# RA6M1.net
KiCad netlist of a schematic drawn in Altium Designer
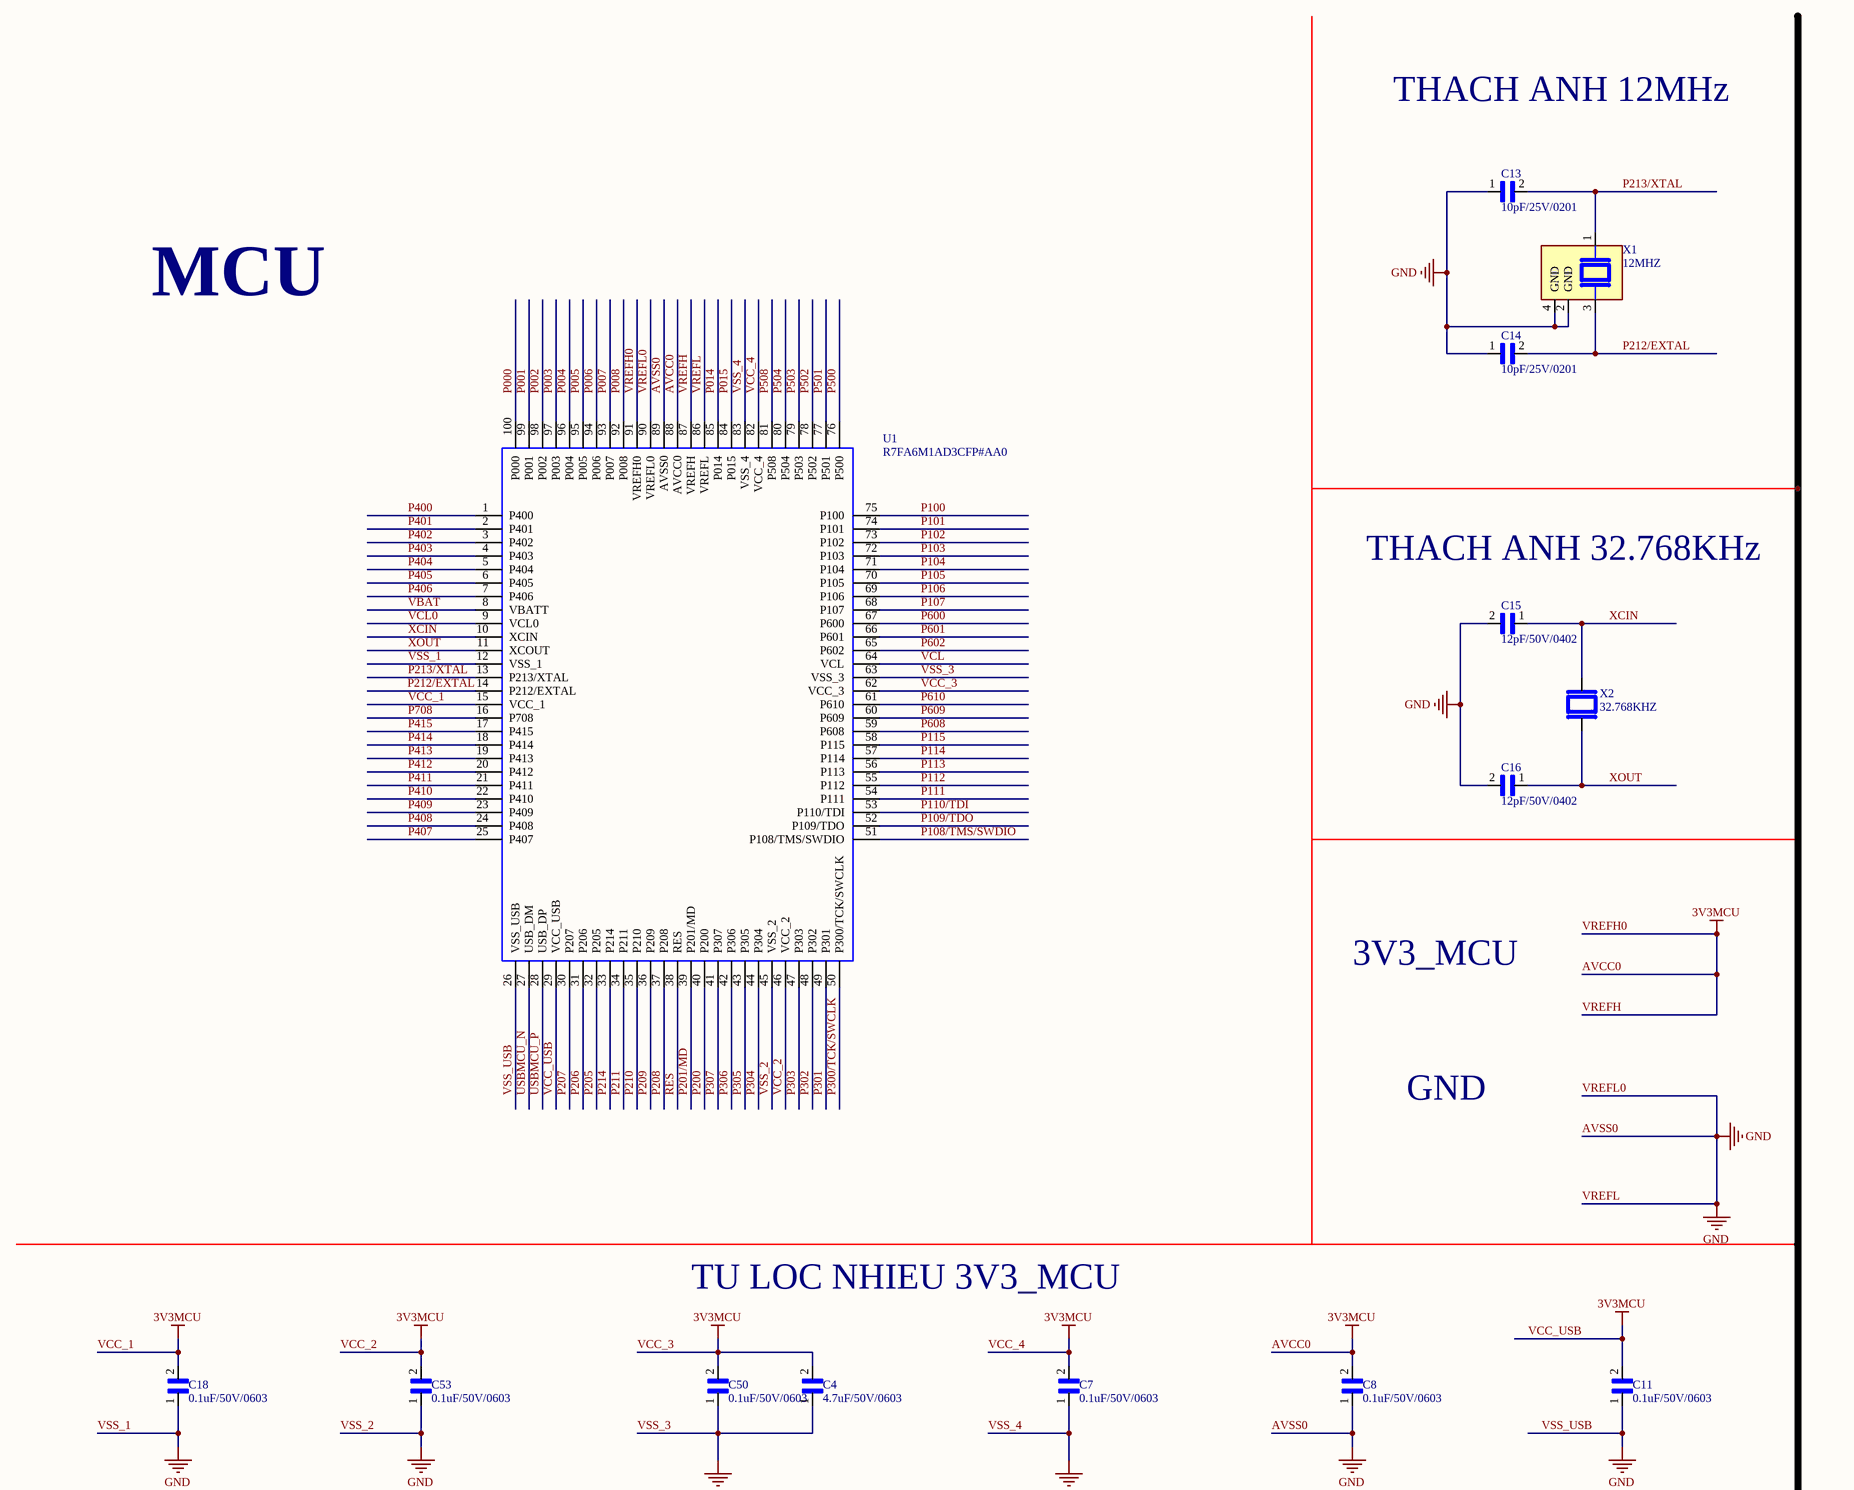
[diagram p0: RA6M1.SchDoc, top left]
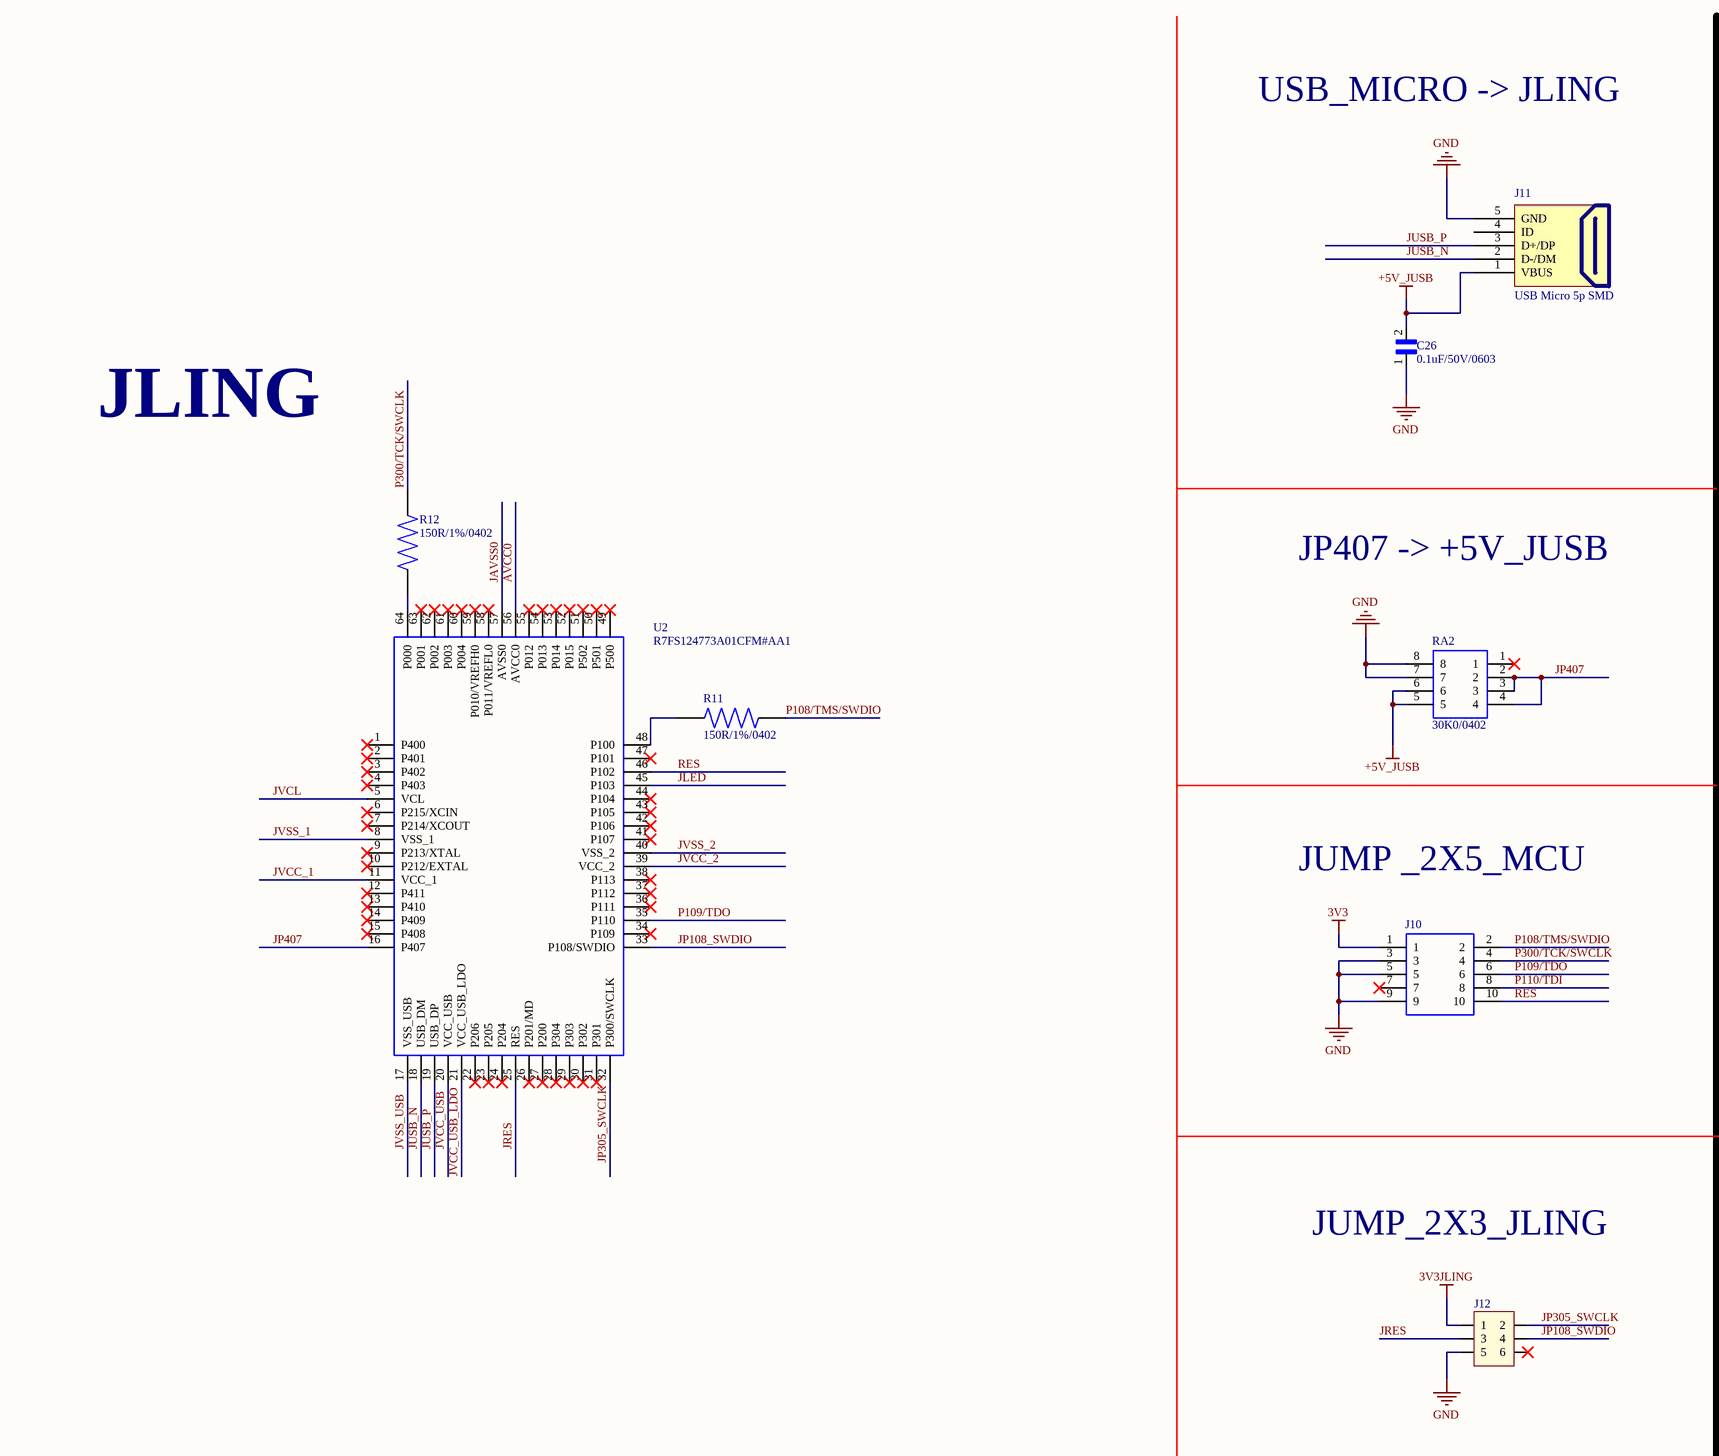
[diagram p1: RA6M1.SchDoc, top middle]
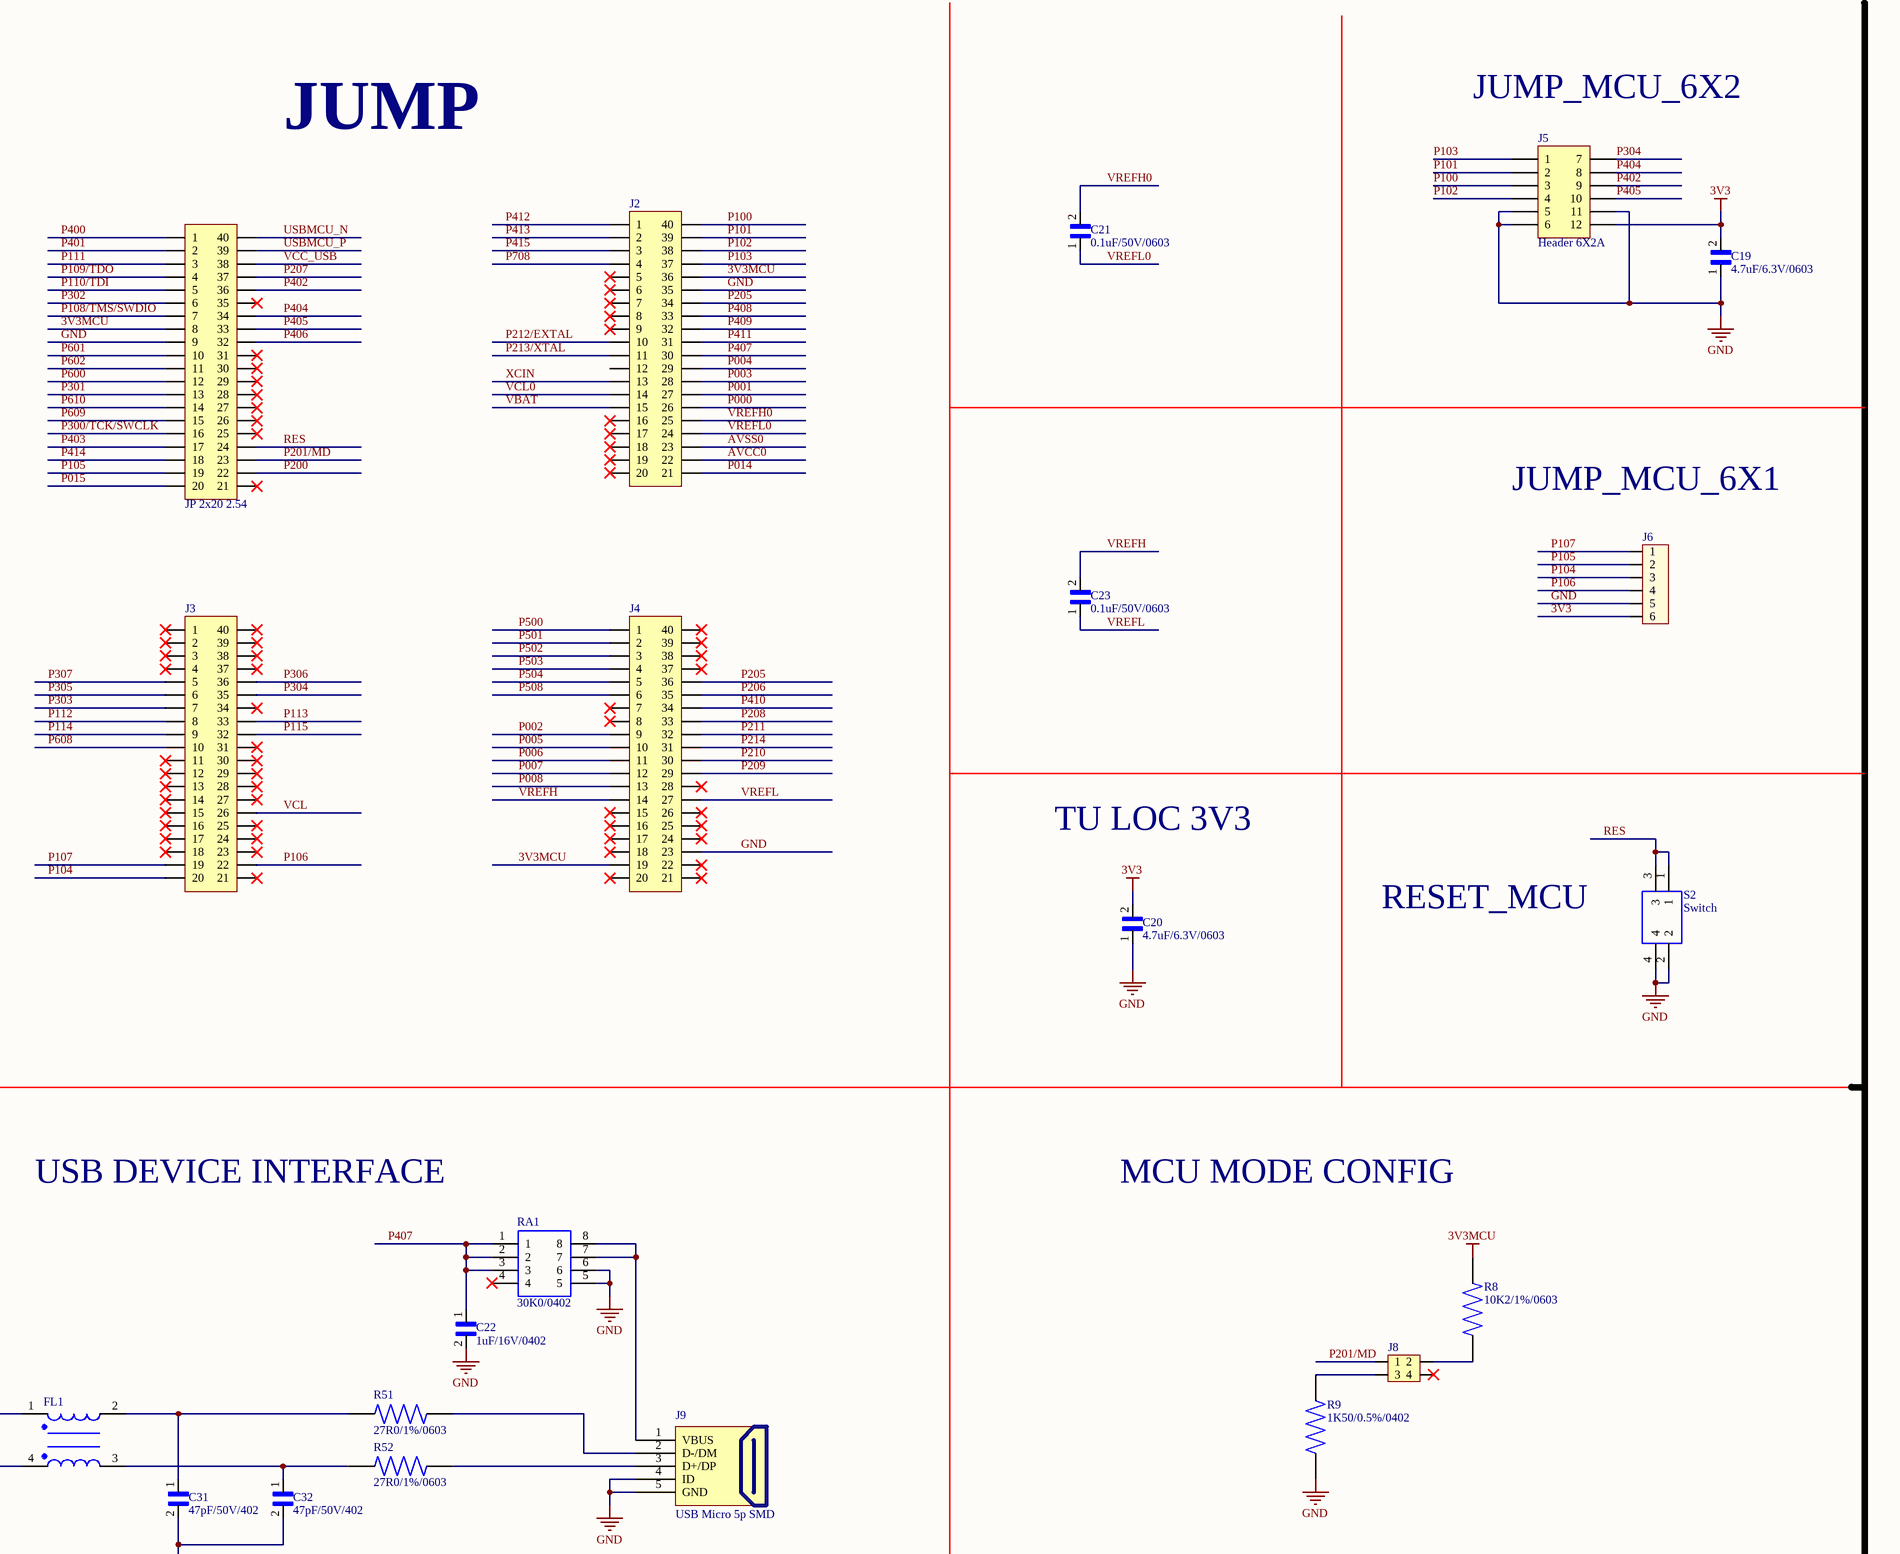
[diagram p2: RA6M1.SchDoc, top right]
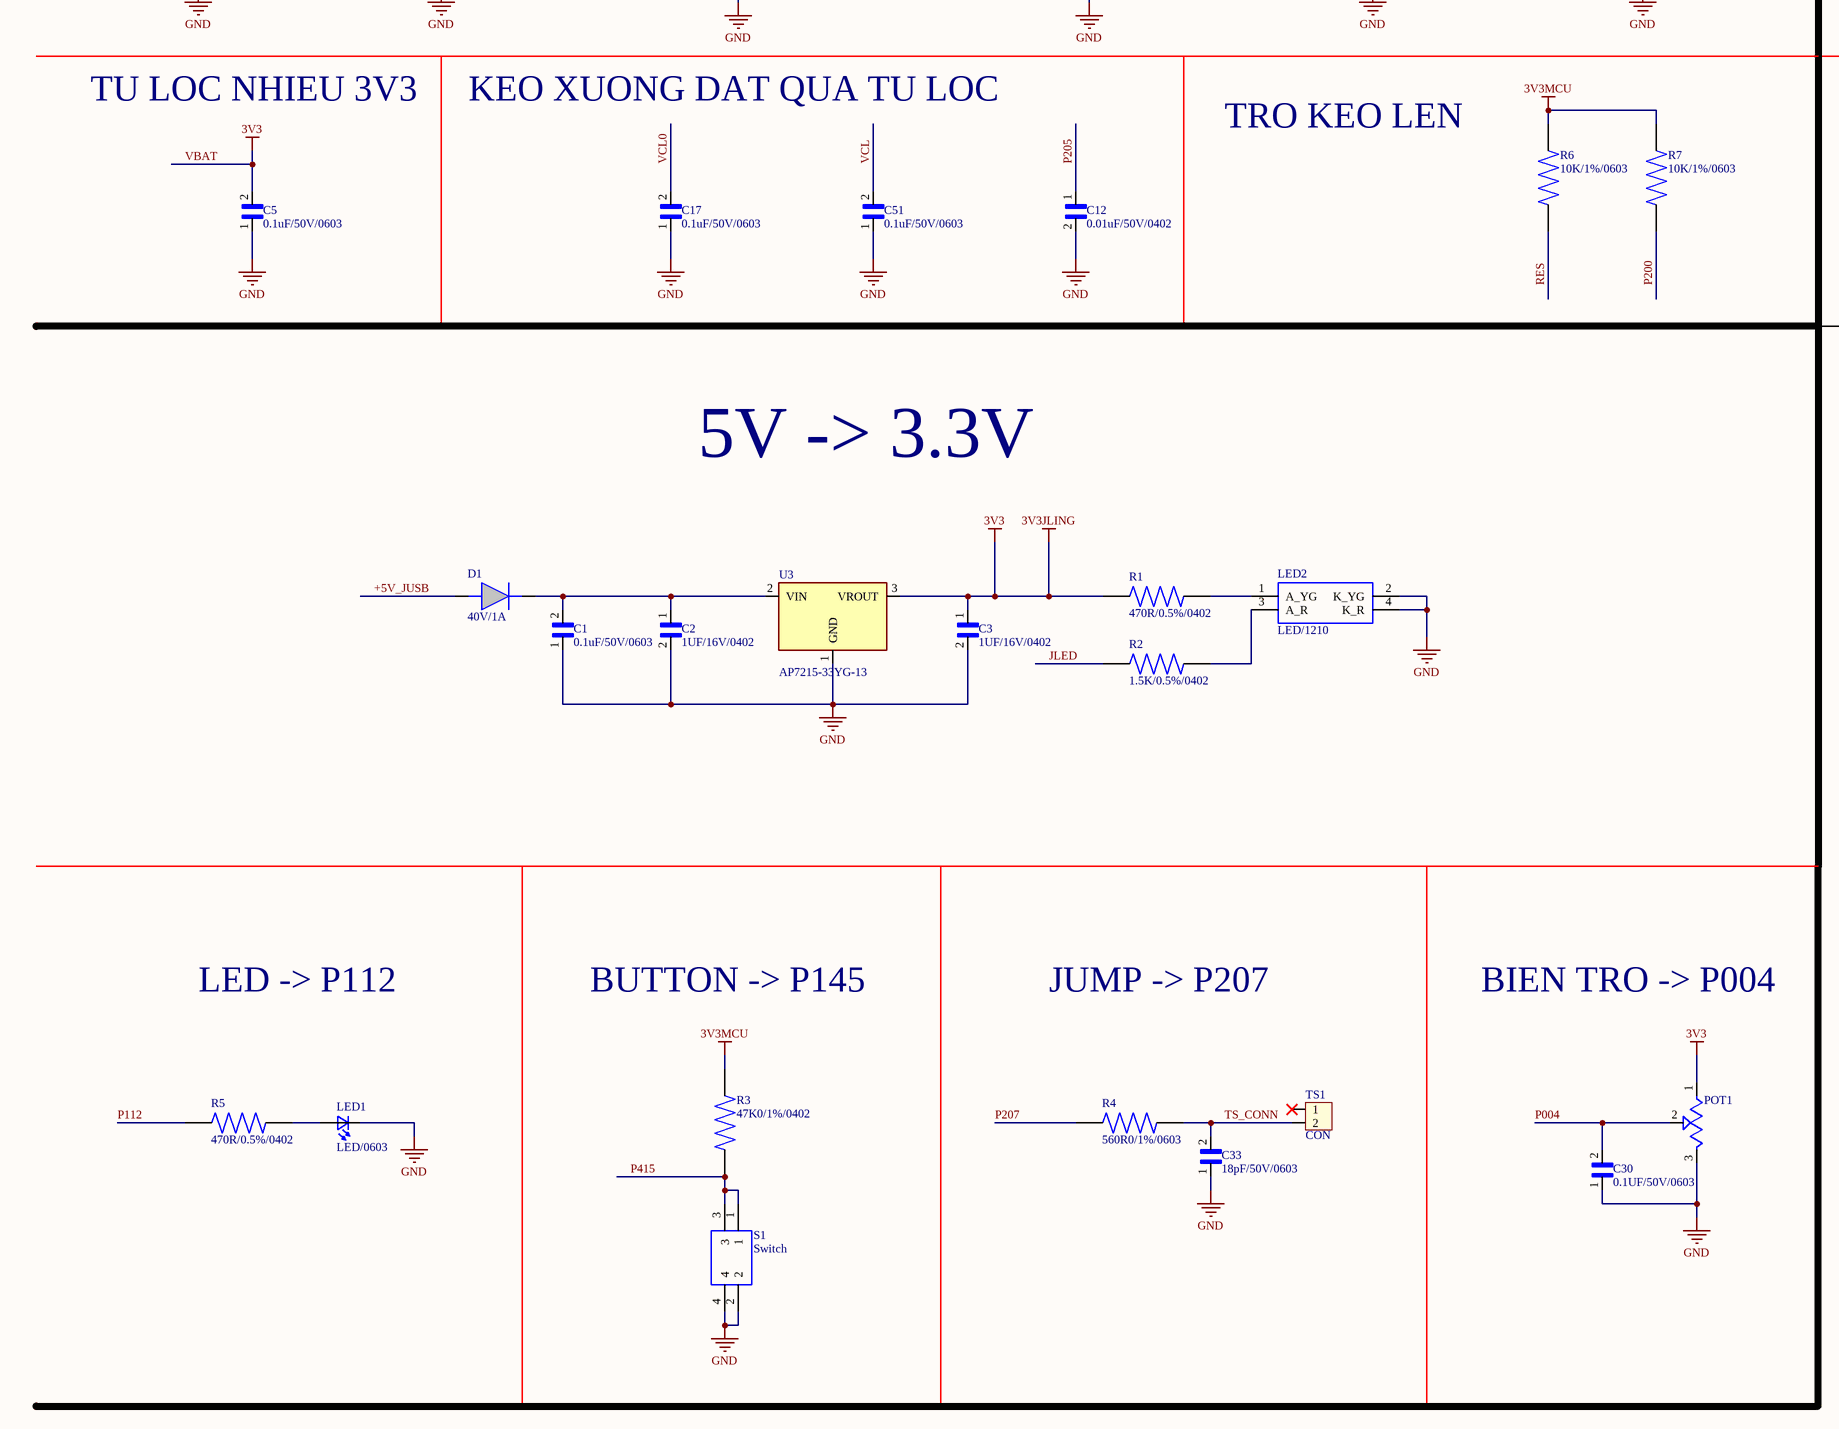
[diagram p3: RA6M1.SchDoc, bottom left]
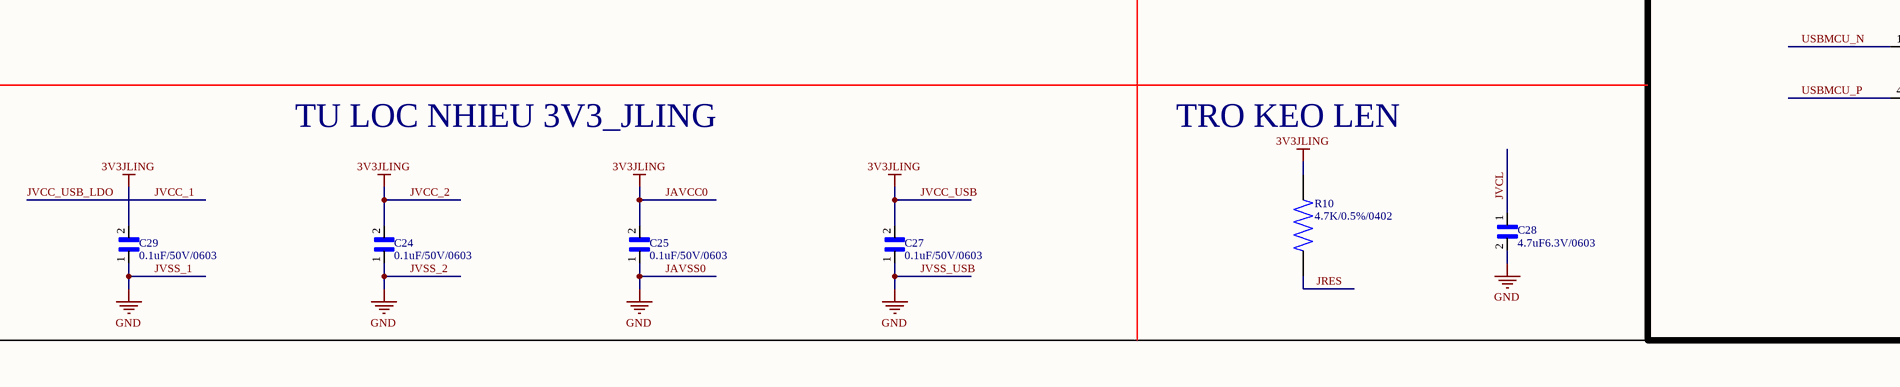
[diagram p4: RA6M1.SchDoc, bottom middle]
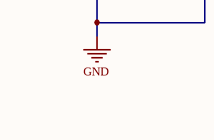
[diagram p5: RA6M1.SchDoc, bottom right]

(export (version "E")
  (design (tool "Eeschema 10.0.6"))
  (components
    (comp (ref "C1")
      (value "0.1uF/50V/0603")
      (footprint "CAPC1608X90N")
      (description "0.1ÂµF Â±10% 50V Ceramic Capacitor X7R 0603 _1608 Metric_")
      (fields (field (name "MP") "CL10B104KB8NNNC") (field (name "MF") "Samsung Electro-Mechanics"))
      (libsource (lib "RA6M1_DONE") (part "CL10B104KB8NNNC"))
    )
    (comp (ref "C2")
      (value "1UF/16V/0402")
      (footprint "CAPC1005X55N")
      (description "1ÂµF Â±10% 16V Ceramic Capacitor X5R 0402 (1005 Metric)")
      (fields (field (name "MP") "CL05A105KO5NNNC") (field (name "MF") "Samsung Electro-Mechanics"))
      (libsource (lib "RA6M1_DONE") (part "CL05A105KO5NNNC"))
    )
    (comp (ref "C3")
      (value "1UF/16V/0402")
      (footprint "CAPC1005X55N")
      (description "1ÂµF Â±10% 16V Ceramic Capacitor X5R 0402 (1005 Metric)")
      (fields (field (name "MP") "CL05A105KO5NNNC") (field (name "MF") "Samsung Electro-Mechanics"))
      (libsource (lib "RA6M1_DONE") (part "CL05A105KO5NNNC"))
    )
    (comp (ref "C4")
      (value "4.7uF/50V/0603")
      (footprint "CAPC1608X90N")
      (description "0.1ÂµF Â±10% 50V Ceramic Capacitor X7R 0603 _1608 Metric_")
      (fields (field (name "MP") "CL10B104KB8NNNC") (field (name "MF") "Samsung Electro-Mechanics"))
      (libsource (lib "RA6M1_DONE") (part "CL10B104KB8NNNC"))
    )
    (comp (ref "C5")
      (value "0.1uF/50V/0603")
      (footprint "CAPC1608X90N")
      (description "0.1ÂµF Â±10% 50V Ceramic Capacitor X7R 0603 _1608 Metric_")
      (fields (field (name "MP") "CL10B104KB8NNNC") (field (name "MF") "Samsung Electro-Mechanics"))
      (libsource (lib "RA6M1_DONE") (part "CL10B104KB8NNNC"))
    )
    (comp (ref "C7")
      (value "0.1uF/50V/0603")
      (footprint "CAPC1608X90N")
      (description "0.1ÂµF Â±10% 50V Ceramic Capacitor X7R 0603 _1608 Metric_")
      (fields (field (name "MP") "CL10B104KB8NNNC") (field (name "MF") "Samsung Electro-Mechanics"))
      (libsource (lib "RA6M1_DONE") (part "CL10B104KB8NNNC"))
    )
    (comp (ref "C8")
      (value "0.1uF/50V/0603")
      (footprint "CAPC1608X90N")
      (description "0.1ÂµF Â±10% 50V Ceramic Capacitor X7R 0603 _1608 Metric_")
      (fields (field (name "MP") "CL10B104KB8NNNC") (field (name "MF") "Samsung Electro-Mechanics"))
      (libsource (lib "RA6M1_DONE") (part "CL10B104KB8NNNC"))
    )
    (comp (ref "C11")
      (value "0.1uF/50V/0603")
      (footprint "CAPC1608X90N")
      (description "0.1ÂµF Â±10% 50V Ceramic Capacitor X7R 0603 _1608 Metric_")
      (fields (field (name "MP") "CL10B104KB8NNNC") (field (name "MF") "Samsung Electro-Mechanics"))
      (libsource (lib "RA6M1_DONE") (part "CL10B104KB8NNNC"))
    )
    (comp (ref "C12")
      (value "0.01uF/50V/0402")
      (footprint "CAPC1005X55N")
      (description "1ÂµF Â±10% 16V Ceramic Capacitor X5R 0402 (1005 Metric)")
      (fields (field (name "MP") "CL05A105KO5NNNC") (field (name "MF") "Samsung Electro-Mechanics"))
      (libsource (lib "RA6M1_DONE") (part "CL05A105KO5NNNC"))
    )
    (comp (ref "C13")
      (value "10pF/25V/0201")
      (footprint "RESC0603X26N")
      (description "TU0201")
      (fields (field (name "MP") "CL10B104KB8NNNC") (field (name "MF") "Samsung Electro-Mechanics"))
      (libsource (lib "Tu0201") (part "RESC0603X26N"))
    )
    (comp (ref "C14")
      (value "10pF/25V/0201")
      (footprint "RESC0603X26N")
      (description "TU0201")
      (fields (field (name "MP") "CL10B104KB8NNNC") (field (name "MF") "Samsung Electro-Mechanics"))
      (libsource (lib "Tu0201") (part "RESC0603X26N"))
    )
    (comp (ref "C15")
      (value "12pF/50V/0402")
      (footprint "CAPC1005X55N")
      (description "1ÂµF Â±10% 16V Ceramic Capacitor X5R 0402 (1005 Metric)")
      (fields (field (name "MP") "CL05A105KO5NNNC") (field (name "MF") "Samsung Electro-Mechanics"))
      (libsource (lib "") (part "CL05A105KO5NNNC_1"))
    )
    (comp (ref "C16")
      (value "12pF/50V/0402")
      (footprint "CAPC1005X55N")
      (description "1ÂµF Â±10% 16V Ceramic Capacitor X5R 0402 (1005 Metric)")
      (fields (field (name "MP") "CL05A105KO5NNNC") (field (name "MF") "Samsung Electro-Mechanics"))
      (libsource (lib "") (part "CL05A105KO5NNNC_1"))
    )
    (comp (ref "C17")
      (value "0.1uF/50V/0603")
      (footprint "CAPC1608X90N")
      (description "0.1ÂµF Â±10% 50V Ceramic Capacitor X7R 0603 _1608 Metric_")
      (fields (field (name "MP") "CL10B104KB8NNNC") (field (name "MF") "Samsung Electro-Mechanics"))
      (libsource (lib "RA6M1_DONE") (part "CL10B104KB8NNNC"))
    )
    (comp (ref "C18")
      (value "0.1uF/50V/0603")
      (footprint "CAPC1608X90N")
      (description "0.1ÂµF Â±10% 50V Ceramic Capacitor X7R 0603 _1608 Metric_")
      (fields (field (name "MP") "CL10B104KB8NNNC") (field (name "MF") "Samsung Electro-Mechanics"))
      (libsource (lib "RA6M1_DONE") (part "CL10B104KB8NNNC"))
    )
    (comp (ref "C19")
      (value "4.7uF/6.3V/0603")
      (footprint "CAPC1608X90N")
      (description "0.1ÂµF Â±10% 50V Ceramic Capacitor X7R 0603 _1608 Metric_")
      (fields (field (name "MP") "CL10B104KB8NNNC") (field (name "MF") "Samsung Electro-Mechanics"))
      (libsource (lib "RA6M1_DONE") (part "CL10B104KB8NNNC"))
    )
    (comp (ref "C20")
      (value "4.7uF/6.3V/0603")
      (footprint "CAPC1608X90N")
      (description "0.1ÂµF Â±10% 50V Ceramic Capacitor X7R 0603 _1608 Metric_")
      (fields (field (name "MP") "CL10B104KB8NNNC") (field (name "MF") "Samsung Electro-Mechanics"))
      (libsource (lib "RA6M1_DONE") (part "CL10B104KB8NNNC"))
    )
    (comp (ref "C21")
      (value "0.1uF/50V/0603")
      (footprint "CAPC1608X90N")
      (description "0.1ÂµF Â±10% 50V Ceramic Capacitor X7R 0603 _1608 Metric_")
      (fields (field (name "MP") "CL10B104KB8NNNC") (field (name "MF") "Samsung Electro-Mechanics"))
      (libsource (lib "RA6M1_DONE") (part "CL10B104KB8NNNC"))
    )
    (comp (ref "C22")
      (value "1uF/16V/0402")
      (footprint "CAPC1005X55N")
      (description "1ÂµF Â±10% 16V Ceramic Capacitor X5R 0402 (1005 Metric)")
      (fields (field (name "MP") "CL05A105KO5NNNC") (field (name "MF") "Samsung Electro-Mechanics"))
      (libsource (lib "RA6M1_DONE") (part "CL05A105KO5NNNC"))
    )
    (comp (ref "C23")
      (value "0.1uF/50V/0603")
      (footprint "CAPC1608X90N")
      (description "0.1ÂµF Â±10% 50V Ceramic Capacitor X7R 0603 _1608 Metric_")
      (fields (field (name "MP") "CL10B104KB8NNNC") (field (name "MF") "Samsung Electro-Mechanics"))
      (libsource (lib "RA6M1_DONE") (part "CL10B104KB8NNNC"))
    )
    (comp (ref "C24")
      (value "0.1uF/50V/0603")
      (footprint "CAPC1608X90N")
      (description "0.1ÂµF Â±10% 50V Ceramic Capacitor X7R 0603 _1608 Metric_")
      (fields (field (name "MP") "CL10B104KB8NNNC") (field (name "MF") "Samsung Electro-Mechanics"))
      (libsource (lib "RA6M1_DONE") (part "CL10B104KB8NNNC"))
    )
    (comp (ref "C25")
      (value "0.1uF/50V/0603")
      (footprint "CAPC1608X90N")
      (description "0.1ÂµF Â±10% 50V Ceramic Capacitor X7R 0603 _1608 Metric_")
      (fields (field (name "MP") "CL10B104KB8NNNC") (field (name "MF") "Samsung Electro-Mechanics"))
      (libsource (lib "RA6M1_DONE") (part "CL10B104KB8NNNC"))
    )
    (comp (ref "C26")
      (value "0.1uF/50V/0603")
      (footprint "CAPC1608X90N")
      (description "0.1ÂµF Â±10% 50V Ceramic Capacitor X7R 0603 _1608 Metric_")
      (fields (field (name "MP") "CL10B104KB8NNNC") (field (name "MF") "Samsung Electro-Mechanics"))
      (libsource (lib "RA6M1_DONE") (part "CL10B104KB8NNNC"))
    )
    (comp (ref "C27")
      (value "0.1uF/50V/0603")
      (footprint "CAPC1608X90N")
      (description "0.1ÂµF Â±10% 50V Ceramic Capacitor X7R 0603 _1608 Metric_")
      (fields (field (name "MP") "CL10B104KB8NNNC") (field (name "MF") "Samsung Electro-Mechanics"))
      (libsource (lib "RA6M1_DONE") (part "CL10B104KB8NNNC"))
    )
    (comp (ref "C28")
      (value "4.7uF6.3V/0603")
      (footprint "CAPC1608X90N")
      (description "0.1ÂµF Â±10% 50V Ceramic Capacitor X7R 0603 _1608 Metric_")
      (fields (field (name "MP") "CL10B104KB8NNNC") (field (name "MF") "Samsung Electro-Mechanics"))
      (libsource (lib "") (part "CL10B104KB8NNNC_1"))
    )
    (comp (ref "C29")
      (value "0.1uF/50V/0603")
      (footprint "CAPC1608X90N")
      (description "0.1ÂµF Â±10% 50V Ceramic Capacitor X7R 0603 _1608 Metric_")
      (fields (field (name "MP") "CL10B104KB8NNNC") (field (name "MF") "Samsung Electro-Mechanics"))
      (libsource (lib "RA6M1_DONE") (part "CL10B104KB8NNNC"))
    )
    (comp (ref "C30")
      (value "0.1UF/50V/0603")
      (footprint "CAPC1608X90N")
      (description "0.1ÂµF Â±10% 50V Ceramic Capacitor X7R 0603 _1608 Metric_")
      (fields (field (name "MP") "CL10B104KB8NNNC") (field (name "MF") "Samsung Electro-Mechanics"))
      (libsource (lib "RA6M1_DONE") (part "CL10B104KB8NNNC"))
    )
    (comp (ref "C31")
      (value "47pF/50V/402")
      (footprint "CAPC1005X55N")
      (description "1ÂµF Â±10% 16V Ceramic Capacitor X5R 0402 (1005 Metric)")
      (fields (field (name "MP") "CL05A105KO5NNNC") (field (name "MF") "Samsung Electro-Mechanics"))
      (libsource (lib "RA6M1_DONE") (part "CL05A105KO5NNNC"))
    )
    (comp (ref "C32")
      (value "47pF/50V/402")
      (footprint "CAPC1005X55N")
      (description "1ÂµF Â±10% 16V Ceramic Capacitor X5R 0402 (1005 Metric)")
      (fields (field (name "MP") "CL05A105KO5NNNC") (field (name "MF") "Samsung Electro-Mechanics"))
      (libsource (lib "RA6M1_DONE") (part "CL05A105KO5NNNC"))
    )
    (comp (ref "C33")
      (value "18pF/50V/0603")
      (footprint "CAPC1608X90N")
      (description "0.1ÂµF Â±10% 50V Ceramic Capacitor X7R 0603 _1608 Metric_")
      (fields (field (name "MP") "CL10B104KB8NNNC") (field (name "MF") "Samsung Electro-Mechanics"))
      (libsource (lib "RA6M1_DONE") (part "CL10B104KB8NNNC"))
    )
    (comp (ref "C50")
      (value "0.1uF/50V/0603")
      (footprint "CAPC1608X90N")
      (description "0.1ÂµF Â±10% 50V Ceramic Capacitor X7R 0603 _1608 Metric_")
      (fields (field (name "MP") "CL10B104KB8NNNC") (field (name "MF") "Samsung Electro-Mechanics"))
      (libsource (lib "RA6M1_DONE") (part "CL10B104KB8NNNC"))
    )
    (comp (ref "C51")
      (value "0.1uF/50V/0603")
      (footprint "CAPC1608X90N")
      (description "0.1ÂµF Â±10% 50V Ceramic Capacitor X7R 0603 _1608 Metric_")
      (fields (field (name "MP") "CL10B104KB8NNNC") (field (name "MF") "Samsung Electro-Mechanics"))
      (libsource (lib "RA6M1_DONE") (part "CL10B104KB8NNNC"))
    )
    (comp (ref "C53")
      (value "0.1uF/50V/0603")
      (footprint "CAPC1608X90N")
      (description "0.1ÂµF Â±10% 50V Ceramic Capacitor X7R 0603 _1608 Metric_")
      (fields (field (name "MP") "CL10B104KB8NNNC") (field (name "MF") "Samsung Electro-Mechanics"))
      (libsource (lib "RA6M1_DONE") (part "CL10B104KB8NNNC"))
    )
    (comp (ref "D1")
      (value "40V/1A")
      (footprint "SODFL3616X98N")
      (fields
        (field (name "MANUFACTURER_PART_NUMBER") "MBR140SFT1G")
        (field (name "MOUSER PART NUMBER") "863-MBR140SFT1G")
      )
      (libsource (lib "RA6M1_DONE") (part "MBR140SFT1G"))
    )
    (comp (ref "FL1")
      (value "DLP11SN201HL2L")
      (footprint "FIL_DLP11SN201HL2L")
      (description "2 Line Common Mode Choke Surface Mount 200 Ohms @ 100MHz 110mA DCR 3.88Ohm")
      (fields (field (name "MF") "Murata"))
      (libsource (lib "RA6M1_DONE") (part "DLP11SN201HL2L"))
    )
    (comp (ref "J1")
      (value "JP 2x20 2.54")
      (footprint "JP 2x20 DT")
      (description "Cắm")
      (libsource (lib "Altium_Lib_by_KhueNguyenCreator") (part "JP 2x20 2.54 Duc Thang"))
    )
    (comp (ref "J2")
      (value "JP 2x20 2.54")
      (footprint "JP 2x20 DT")
      (description "Cắm")
      (libsource (lib "Altium_Lib_by_KhueNguyenCreator") (part "JP 2x20 2.54 Duc Thang"))
    )
    (comp (ref "J3")
      (value "JP 2x20 2.54")
      (footprint "JP 2x20 DT")
      (description "Cắm")
      (libsource (lib "Altium_Lib_by_KhueNguyenCreator") (part "JP 2x20 2.54 Duc Thang"))
    )
    (comp (ref "J4")
      (value "JP 2x20 2.54")
      (footprint "JP 2x20 DT")
      (description "Cắm")
      (libsource (lib "Altium_Lib_by_KhueNguyenCreator") (part "JP 2x20 2.54 Duc Thang"))
    )
    (comp (ref "J5")
      (value "Header 6X2A")
      (footprint "HDR2X6_CEN")
      (description "Header, 6-Pin, Dual row")
      (fields (field (name "PUBLISHER") "Altium Limited"))
      (libsource (lib "My library altium") (part "Header 6X2A"))
    )
    (comp (ref "J6")
      (value "JP6")
      (footprint "jam6")
      (description "jam 6")
      (libsource (lib "My library altium") (part "jam 6"))
    )
    (comp (ref "J8")
      (value "JP2x2")
      (footprint "HDR2X2")
      (libsource (lib "My library altium") (part "JP2x2"))
    )
    (comp (ref "J9")
      (value "USB Micro 5p SMD")
      (footprint "USB Micro 5p SMD")
      (description "USB Type B")
      (libsource (lib "Altium_Lib_by_KhueNguyenCreator") (part "USB Micro 5p SMD"))
    )
    (comp (ref "J10")
      (value "3220-10-0100-00")
      (footprint "322010010000")
      (description "Conn Shrouded Header (4 Sides) HDR 10 POS 1.27mm Solder ST Thru-Hole")
      (libsource (lib "RA6M1_DONE") (part "3220-10-0100-00"))
    )
    (comp (ref "J11")
      (value "USB Micro 5p SMD")
      (footprint "USB Micro 5p SMD")
      (description "USB Type B")
      (libsource (lib "") (part "USB Micro 5p SMD_1"))
    )
    (comp (ref "J12")
      (value "HEAD 3x2")
      (footprint "HDR2X3")
      (description "Connector 3x2")
      (libsource (lib "My library altium") (part "JP3x2"))
    )
    (comp (ref "LED1")
      (value "LED/0603")
      (footprint "0603")
      (description "http://octopart.com/ltst-c190krkt-lite-on-549893")
      (fields (field (name "MP") "LTST-C191KRKT"))
      (libsource (lib "RA6M1_DONE") (part "LTST-C191KRKT"))
    )
    (comp (ref "LED2")
      (value "LED/1210")
      (footprint "LED_597-7701-507F")
      (description "Standard LEDs - SMD Red/Green WC 80/50mcd 645/570nm")
      (fields
        (field (name "MANUFACTURER_PART_NUMBER") "598-8610-207F")
        (field (name "MOUSER PART NUMBER") "645-598-8610-207F")
      )
      (libsource (lib "RA6M1_DONE") (part "598-8610-207F"))
    )
    (comp (ref "POT1")
      (value "10K0")
      (footprint "TRIM_3352T-1-103LF")
      (description "10 kOhms 0.5W, 1/2W Through Hole Thumbwheel Potentiometer Top Adjustment")
      (fields (field (name "MP") "3352T-1-103LF") (field (name "MF") "Bourns"))
      (libsource (lib "RA6M1_DONE") (part "3352T-1-103LF"))
    )
    (comp (ref "R1")
      (value "470R/0.5%/0402")
      (footprint "RES_ERA2AED472X")
      (description "Res Thin Film 0402 4.7K Ohm 0.5% 0.063W(1/16W) 25ppm/C Molded SMD Automotive Punched T/R")
      (fields (field (name "MF") "Panasonic Electronic") (field (name "MP") "ERA-2AED472X"))
      (libsource (lib "RA6M1_DONE") (part "ERA2AED472X"))
    )
    (comp (ref "R2")
      (value "1.5K/0.5%/0402")
      (footprint "RES_ERA2AED472X")
      (description "Res Thin Film 0402 4.7K Ohm 0.5% 0.063W(1/16W) 25ppm/C Molded SMD Automotive Punched T/R")
      (fields (field (name "MF") "Panasonic Electronic") (field (name "MP") "ERA-2AED472X"))
      (libsource (lib "RA6M1_DONE") (part "ERA2AED472X"))
    )
    (comp (ref "R3")
      (value "47K0/1%/0402")
      (footprint "RES_ERA2AED472X")
      (description "Res Thin Film 0402 4.7K Ohm 0.5% 0.063W(1/16W) 25ppm/C Molded SMD Automotive Punched T/R")
      (fields (field (name "MF") "Panasonic Electronic") (field (name "MP") "ERA-2AED472X"))
      (libsource (lib "RA6M1_DONE") (part "ERA2AED472X"))
    )
    (comp (ref "R4")
      (value "560R0/1%/0603")
      (footprint "RESC1508X55N")
      (fields (field (name "MP") "RMCF0603JT27R0"))
      (libsource (lib "RA6M1_DONE") (part "RMCF0603JT27R0"))
    )
    (comp (ref "R5")
      (value "470R/0.5%/0402")
      (footprint "RES_ERA2AED472X")
      (description "Res Thin Film 0402 4.7K Ohm 0.5% 0.063W(1/16W) 25ppm/C Molded SMD Automotive Punched T/R")
      (fields (field (name "MF") "Panasonic Electronic") (field (name "MP") "ERA-2AED472X"))
      (libsource (lib "RA6M1_DONE") (part "ERA2AED472X"))
    )
    (comp (ref "R6")
      (value "10K/1%/0603")
      (footprint "RESC1508X55N")
      (fields (field (name "MP") "RMCF0603JT27R0"))
      (libsource (lib "RA6M1_DONE") (part "RMCF0603JT27R0"))
    )
    (comp (ref "R7")
      (value "10K/1%/0603")
      (footprint "RESC1508X55N")
      (fields (field (name "MP") "RMCF0603JT27R0"))
      (libsource (lib "RA6M1_DONE") (part "RMCF0603JT27R0"))
    )
    (comp (ref "R8")
      (value "10K2/1%/0603")
      (footprint "RESC1508X55N")
      (fields (field (name "MP") "RMCF0603JT27R0"))
      (libsource (lib "RA6M1_DONE") (part "RMCF0603JT27R0"))
    )
    (comp (ref "R9")
      (value "1K50/0.5%/0402")
      (footprint "RES_ERA2AED472X")
      (description "Res Thin Film 0402 4.7K Ohm 0.5% 0.063W(1/16W) 25ppm/C Molded SMD Automotive Punched T/R")
      (fields (field (name "MF") "Panasonic Electronic") (field (name "MP") "ERA-2AED472X"))
      (libsource (lib "RA6M1_DONE") (part "ERA2AED472X"))
    )
    (comp (ref "R10")
      (value "4.7K/0.5%/0402")
      (footprint "RES_ERA2AED472X")
      (description "Res Thin Film 0402 4.7K Ohm 0.5% 0.063W(1/16W) 25ppm/C Molded SMD Automotive Punched T/R")
      (fields (field (name "MF") "Panasonic Electronic") (field (name "MP") "ERA-2AED472X"))
      (libsource (lib "RA6M1_DONE") (part "ERA2AED472X"))
    )
    (comp (ref "R11")
      (value "150R/1%/0402")
      (footprint "RES_ERA2AED472X")
      (description "Res Thin Film 0402 4.7K Ohm 0.5% 0.063W(1/16W) 25ppm/C Molded SMD Automotive Punched T/R")
      (fields (field (name "MF") "Panasonic Electronic") (field (name "MP") "ERA-2AED472X"))
      (libsource (lib "RA6M1_DONE") (part "ERA2AED472X"))
    )
    (comp (ref "R12")
      (value "150R/1%/0402")
      (footprint "RES_ERA2AED472X")
      (description "Res Thin Film 0402 4.7K Ohm 0.5% 0.063W(1/16W) 25ppm/C Molded SMD Automotive Punched T/R")
      (fields (field (name "MF") "Panasonic Electronic") (field (name "MP") "ERA-2AED472X"))
      (libsource (lib "RA6M1_DONE") (part "ERA2AED472X"))
    )
    (comp (ref "R51")
      (value "27R0/1%/0603")
      (footprint "RESC1508X55N")
      (fields (field (name "MP") "RMCF0603JT27R0"))
      (libsource (lib "RA6M1_DONE") (part "RMCF0603JT27R0"))
    )
    (comp (ref "R52")
      (value "27R0/1%/0603")
      (footprint "RESC1508X55N")
      (fields (field (name "MP") "RMCF0603JT27R0"))
      (libsource (lib "RA6M1_DONE") (part "RMCF0603JT27R0"))
    )
    (comp (ref "RA1")
      (value "30K0/0402")
      (footprint "EXB28V510JX")
      (description "Resistor Networks & Arrays Resistor ArrayChip 0804 4 elements")
      (fields (field (name "MANUFACTURER_PART_NUMBER") "EXB28V303JX"))
      (libsource (lib "RA6M1_DONE") (part "EXB28V303JX"))
    )
    (comp (ref "RA2")
      (value "30K0/0402")
      (footprint "EXB28V510JX")
      (description "Resistor Networks & Arrays Resistor ArrayChip 0804 4 elements")
      (fields (field (name "MANUFACTURER_PART_NUMBER") "EXB28V303JX"))
      (libsource (lib "RA6M1_DONE") (part "EXB28V303JX"))
    )
    (comp (ref "S1")
      (value "Switch")
      (footprint "PTS645(SMT)")
      (description "C & K COMPONENTS - PTS645SM43SMTR92LFS - SWITCH, SPST, 0.05A, 12VDC, SMD, 4.3MM")
      (fields
        (field (name "MANUFACTURER_PART_NUMBER") "PTS645SM43SMTR92LFS")
        (field (name "MOUSER PART NUMBER") "611-PTS645SM43SMTR92")
      )
      (libsource (lib "RA6M1_DONE") (part "PTS645SM43SMTR92LFS"))
    )
    (comp (ref "S2")
      (value "Switch")
      (footprint "PTS645(SMT)")
      (description "C & K COMPONENTS - PTS645SM43SMTR92LFS - SWITCH, SPST, 0.05A, 12VDC, SMD, 4.3MM")
      (fields
        (field (name "MANUFACTURER_PART_NUMBER") "PTS645SM43SMTR92LFS")
        (field (name "MOUSER PART NUMBER") "611-PTS645SM43SMTR92")
      )
      (libsource (lib "RA6M1_DONE") (part "PTS645SM43SMTR92LFS"))
    )
    (comp (ref "TS1")
      (value "CON")
      (footprint "CON2")
      (description "connector 2")
      (libsource (lib "My library altium") (part "Con2"))
    )
    (comp (ref "U1")
      (value "R7FA6M1AD3CFP#AA0")
      (footprint "QFP50P1600X1600X170-100N")
      (description "ARM Cortex-M4 RA6M1 Microcontroller IC 32-Bit 120MHz 512KB (512K x 8) FLASH 100-LFQFP (14x14)")
      (fields (field (name "MOUSER PART NUMBER") "968-7FA6M1AD3CFP#AA0"))
      (libsource (lib "RA6M1_DONE") (part "R7FA6M1AD3CFP#AA0"))
    )
    (comp (ref "U2")
      (value "R7FS124773A01CFM#AA1")
      (footprint "QFP50P1200X1200X170-64N")
      (description "S124")
      (fields (field (name "MOUSER PART NUMBER") "968-124773A01CFM#AA1"))
      (libsource (lib "RA6M1_DONE") (part "R7FS124773A01CFM#AA1"))
    )
    (comp (ref "U3")
      (value "AP7215-33YG-13")
      (footprint "SOT150P400X160-3N")
      (description "Linear Voltage Regulator IC 1 Output 600mA SOT-89-3")
      (fields (field (name "MF") "Diodes Inc."))
      (libsource (lib "RA6M1_DONE") (part "AP7215-33YG-13"))
    )
    (comp (ref "X1")
      (value "12MHZ")
      (footprint "XTAL_ABM8G-12.000MHZ-B4Y-T")
      (description "12 MHz Â±30ppm Crystal 10pF 120 Ohms 4-SMD, No Lead")
      (fields (field (name "MP") "ABM8G-12.000MHZ-B4Y-T") (field (name "MF") "Abracon"))
      (libsource (lib "RA6M1_DONE") (part "ABM8G-12.000MHZ-B4Y-T"))
    )
    (comp (ref "X2")
      (value "32.768KHZ")
      (footprint "XTAL_ABS07-32.768KHZ-T")
      (description "32.768 kHz Â±20ppm Crystal 12.5pF 70 kOhms 2-SMD, No Lead")
      (fields (field (name "MP") "ABS07-32.768KHZ-T") (field (name "MF") "Abracon"))
      (libsource (lib "RA6M1_DONE") (part "ABS07-32.768KHZ-T"))
    )
  )
  (nets
    (net (code "1") (name "+5V_JUSB") (class "Default")
      (node (ref "C26") (pin "2") (pinfunction "2_2") (pintype "passive"))
      (node (ref "D1") (pin "2") (pinfunction "A_2") (pintype "passive"))
      (node (ref "J11") (pin "1") (pinfunction "VBUS_1") (pintype "passive"))
      (node (ref "RA2") (pin "5") (pinfunction "5_5") (pintype "passive"))
      (node (ref "RA2") (pin "6") (pinfunction "6_6") (pintype "passive"))
    )
    (net (code "2") (name "/JLED") (class "Default")
      (node (ref "R2") (pin "1") (pinfunction "1_1") (pintype "passive"))
      (node (ref "U2") (pin "45") (pinfunction "P103_45") (pintype "passive"))
    )
    (net (code "3") (name "/JP108_SWDIO") (class "Default")
      (node (ref "J12") (pin "4") (pinfunction "4_4") (pintype "passive"))
      (node (ref "U2") (pin "33") (pinfunction "P108/SWDIO_33") (pintype "passive"))
    )
    (net (code "4") (name "/JP305_SWCLK") (class "Default")
      (node (ref "J12") (pin "2") (pinfunction "2_2") (pintype "passive"))
      (node (ref "U2") (pin "32") (pinfunction "P300/SWCLK_32") (pintype "passive"))
    )
    (net (code "5") (name "/JP407") (class "Default")
      (node (ref "RA2") (pin "2") (pinfunction "2_2") (pintype "passive"))
      (node (ref "RA2") (pin "3") (pinfunction "3_3") (pintype "passive"))
      (node (ref "RA2") (pin "4") (pinfunction "4_4") (pintype "passive"))
      (node (ref "U2") (pin "16") (pinfunction "P407_16") (pintype "passive"))
    )
    (net (code "6") (name "/JRES") (class "Default")
      (node (ref "J12") (pin "3") (pinfunction "3_3") (pintype "passive"))
      (node (ref "R10") (pin "1") (pinfunction "1_1") (pintype "passive"))
      (node (ref "U2") (pin "25") (pinfunction "RES_25") (pintype "passive"))
    )
    (net (code "7") (name "/JUSB_N") (class "Default")
      (node (ref "J11") (pin "2") (pinfunction "D-/DM_2") (pintype "passive"))
      (node (ref "U2") (pin "18") (pinfunction "USB_DM_18") (pintype "passive"))
    )
    (net (code "8") (name "/JUSB_P") (class "Default")
      (node (ref "J11") (pin "3") (pinfunction "D+/DP_3") (pintype "passive"))
      (node (ref "U2") (pin "19") (pinfunction "USB_DP_19") (pintype "passive"))
    )
    (net (code "9") (name "/JVCC_1") (class "Default")
      (node (ref "U2") (pin "11") (pinfunction "VCC_1_11") (pintype "passive"))
      (node (ref "U2") (pin "21") (pinfunction "VCC_USB_LDO_21") (pintype "passive"))
    )
    (net (code "10") (name "/JVCL") (class "Default")
      (node (ref "C28") (pin "1") (pinfunction "1_1") (pintype "passive"))
      (node (ref "U2") (pin "5") (pinfunction "VCL_5") (pintype "passive"))
    )
    (net (code "11") (name "/P000") (class "Default")
      (node (ref "J2") (pin "26") (pinfunction "26_26") (pintype "passive"))
      (node (ref "U1") (pin "100") (pinfunction "P000_100") (pintype "passive"))
    )
    (net (code "12") (name "/P001") (class "Default")
      (node (ref "J2") (pin "27") (pinfunction "27_27") (pintype "passive"))
      (node (ref "U1") (pin "99") (pinfunction "P001_99") (pintype "passive"))
    )
    (net (code "13") (name "/P002") (class "Default")
      (node (ref "J4") (pin "9") (pinfunction "9_9") (pintype "passive"))
      (node (ref "U1") (pin "98") (pinfunction "P002_98") (pintype "passive"))
    )
    (net (code "14") (name "/P003") (class "Default")
      (node (ref "J2") (pin "28") (pinfunction "28_28") (pintype "passive"))
      (node (ref "U1") (pin "97") (pinfunction "P003_97") (pintype "passive"))
    )
    (net (code "15") (name "/P004") (class "Default")
      (node (ref "C30") (pin "2") (pinfunction "2_2") (pintype "passive"))
      (node (ref "J2") (pin "29") (pinfunction "29_29") (pintype "passive"))
      (node (ref "POT1") (pin "2") (pinfunction "WIPER_2") (pintype "passive"))
      (node (ref "U1") (pin "96") (pinfunction "P004_96") (pintype "passive"))
    )
    (net (code "16") (name "/P005") (class "Default")
      (node (ref "J4") (pin "10") (pinfunction "10_10") (pintype "passive"))
      (node (ref "U1") (pin "95") (pinfunction "P005_95") (pintype "passive"))
    )
    (net (code "17") (name "/P006") (class "Default")
      (node (ref "J4") (pin "11") (pinfunction "11_11") (pintype "passive"))
      (node (ref "U1") (pin "94") (pinfunction "P006_94") (pintype "passive"))
    )
    (net (code "18") (name "/P007") (class "Default")
      (node (ref "J4") (pin "12") (pinfunction "12_12") (pintype "passive"))
      (node (ref "U1") (pin "93") (pinfunction "P007_93") (pintype "passive"))
    )
    (net (code "19") (name "/P008") (class "Default")
      (node (ref "J4") (pin "13") (pinfunction "13_13") (pintype "passive"))
      (node (ref "U1") (pin "92") (pinfunction "P008_92") (pintype "passive"))
    )
    (net (code "20") (name "/P014") (class "Default")
      (node (ref "J2") (pin "21") (pinfunction "21_21") (pintype "passive"))
      (node (ref "U1") (pin "85") (pinfunction "P014_85") (pintype "passive"))
    )
    (net (code "21") (name "/P015") (class "Default")
      (node (ref "J1") (pin "20") (pinfunction "20_20") (pintype "passive"))
      (node (ref "U1") (pin "84") (pinfunction "P015_84") (pintype "passive"))
    )
    (net (code "22") (name "/P100") (class "Default")
      (node (ref "J2") (pin "40") (pinfunction "40_40") (pintype "passive"))
      (node (ref "J5") (pin "3") (pinfunction "3_3") (pintype "passive"))
      (node (ref "U1") (pin "75") (pinfunction "P100_75") (pintype "passive"))
    )
    (net (code "23") (name "/P101") (class "Default")
      (node (ref "J2") (pin "39") (pinfunction "39_39") (pintype "passive"))
      (node (ref "J5") (pin "2") (pinfunction "2_2") (pintype "passive"))
      (node (ref "U1") (pin "74") (pinfunction "P101_74") (pintype "passive"))
    )
    (net (code "24") (name "/P102") (class "Default")
      (node (ref "J2") (pin "38") (pinfunction "38_38") (pintype "passive"))
      (node (ref "J5") (pin "4") (pinfunction "4_4") (pintype "passive"))
      (node (ref "U1") (pin "73") (pinfunction "P102_73") (pintype "passive"))
    )
    (net (code "25") (name "/P103") (class "Default")
      (node (ref "J2") (pin "37") (pinfunction "37_37") (pintype "passive"))
      (node (ref "J5") (pin "1") (pinfunction "1_1") (pintype "passive"))
      (node (ref "U1") (pin "72") (pinfunction "P103_72") (pintype "passive"))
    )
    (net (code "26") (name "/P104") (class "Default")
      (node (ref "J3") (pin "20") (pinfunction "20_20") (pintype "passive"))
      (node (ref "J6") (pin "3") (pinfunction "3_3") (pintype "passive"))
      (node (ref "U1") (pin "71") (pinfunction "P104_71") (pintype "passive"))
    )
    (net (code "27") (name "/P105") (class "Default")
      (node (ref "J1") (pin "19") (pinfunction "19_19") (pintype "passive"))
      (node (ref "J6") (pin "2") (pinfunction "2_2") (pintype "passive"))
      (node (ref "U1") (pin "70") (pinfunction "P105_70") (pintype "passive"))
    )
    (net (code "28") (name "/P106") (class "Default")
      (node (ref "J3") (pin "22") (pinfunction "22_22") (pintype "passive"))
      (node (ref "J6") (pin "4") (pinfunction "4_4") (pintype "passive"))
      (node (ref "U1") (pin "69") (pinfunction "P106_69") (pintype "passive"))
    )
    (net (code "29") (name "/P107") (class "Default")
      (node (ref "J3") (pin "19") (pinfunction "19_19") (pintype "passive"))
      (node (ref "J6") (pin "1") (pinfunction "1_1") (pintype "passive"))
      (node (ref "U1") (pin "68") (pinfunction "P107_68") (pintype "passive"))
    )
    (net (code "30") (name "/P108{slash}TMS{slash}SWDIO") (class "Default")
      (node (ref "J1") (pin "7") (pinfunction "7_7") (pintype "passive"))
      (node (ref "J10") (pin "2") (pinfunction "2_2") (pintype "passive"))
      (node (ref "R11") (pin "2") (pinfunction "2_2") (pintype "passive"))
      (node (ref "U1") (pin "51") (pinfunction "P108/TMS/SWDIO_51") (pintype "passive"))
    )
    (net (code "31") (name "/P109{slash}TDO") (class "Default")
      (node (ref "J1") (pin "4") (pinfunction "4_4") (pintype "passive"))
      (node (ref "J10") (pin "6") (pinfunction "6_6") (pintype "passive"))
      (node (ref "U1") (pin "52") (pinfunction "P109/TDO_52") (pintype "passive"))
      (node (ref "U2") (pin "35") (pinfunction "P110_35") (pintype "passive"))
    )
    (net (code "32") (name "/P110{slash}TDI") (class "Default")
      (node (ref "J1") (pin "5") (pinfunction "5_5") (pintype "passive"))
      (node (ref "J10") (pin "8") (pinfunction "8_8") (pintype "passive"))
      (node (ref "U1") (pin "53") (pinfunction "P110/TDI_53") (pintype "passive"))
    )
    (net (code "33") (name "/P111") (class "Default")
      (node (ref "J1") (pin "3") (pinfunction "3_3") (pintype "passive"))
      (node (ref "U1") (pin "54") (pinfunction "P111_54") (pintype "passive"))
    )
    (net (code "34") (name "/P112") (class "Default")
      (node (ref "J3") (pin "8") (pinfunction "8_8") (pintype "passive"))
      (node (ref "R5") (pin "1") (pinfunction "1_1") (pintype "passive"))
      (node (ref "U1") (pin "55") (pinfunction "P112_55") (pintype "passive"))
    )
    (net (code "35") (name "/P113") (class "Default")
      (node (ref "J3") (pin "33") (pinfunction "33_33") (pintype "passive"))
      (node (ref "U1") (pin "56") (pinfunction "P113_56") (pintype "passive"))
    )
    (net (code "36") (name "/P114") (class "Default")
      (node (ref "J3") (pin "9") (pinfunction "9_9") (pintype "passive"))
      (node (ref "U1") (pin "57") (pinfunction "P114_57") (pintype "passive"))
    )
    (net (code "37") (name "/P115") (class "Default")
      (node (ref "J3") (pin "32") (pinfunction "32_32") (pintype "passive"))
      (node (ref "U1") (pin "58") (pinfunction "P115_58") (pintype "passive"))
    )
    (net (code "38") (name "/P200") (class "Default")
      (node (ref "J1") (pin "22") (pinfunction "22_22") (pintype "passive"))
      (node (ref "R7") (pin "1") (pinfunction "1_1") (pintype "passive"))
      (node (ref "U1") (pin "40") (pinfunction "P200_40") (pintype "passive"))
    )
    (net (code "39") (name "/P201{slash}MD") (class "Default")
      (node (ref "J1") (pin "23") (pinfunction "23_23") (pintype "passive"))
      (node (ref "J8") (pin "1") (pinfunction "1_1") (pintype "passive"))
      (node (ref "U1") (pin "39") (pinfunction "P201/MD_39") (pintype "passive"))
    )
    (net (code "40") (name "/P205") (class "Default")
      (node (ref "C12") (pin "1") (pinfunction "1_1") (pintype "passive"))
      (node (ref "J2") (pin "34") (pinfunction "34_34") (pintype "passive"))
      (node (ref "J4") (pin "36") (pinfunction "36_36") (pintype "passive"))
      (node (ref "U1") (pin "32") (pinfunction "P205_32") (pintype "passive"))
    )
    (net (code "41") (name "/P206") (class "Default")
      (node (ref "J4") (pin "35") (pinfunction "35_35") (pintype "passive"))
      (node (ref "U1") (pin "31") (pinfunction "P206_31") (pintype "passive"))
    )
    (net (code "42") (name "/P207") (class "Default")
      (node (ref "J1") (pin "37") (pinfunction "37_37") (pintype "passive"))
      (node (ref "R4") (pin "1") (pinfunction "1_1") (pintype "passive"))
      (node (ref "U1") (pin "30") (pinfunction "P207_30") (pintype "passive"))
    )
    (net (code "43") (name "/P208") (class "Default")
      (node (ref "J4") (pin "33") (pinfunction "33_33") (pintype "passive"))
      (node (ref "U1") (pin "37") (pinfunction "P208_37") (pintype "passive"))
    )
    (net (code "44") (name "/P209") (class "Default")
      (node (ref "J4") (pin "29") (pinfunction "29_29") (pintype "passive"))
      (node (ref "U1") (pin "36") (pinfunction "P209_36") (pintype "passive"))
    )
    (net (code "45") (name "/P210") (class "Default")
      (node (ref "J4") (pin "30") (pinfunction "30_30") (pintype "passive"))
      (node (ref "U1") (pin "35") (pinfunction "P210_35") (pintype "passive"))
    )
    (net (code "46") (name "/P211") (class "Default")
      (node (ref "J4") (pin "32") (pinfunction "32_32") (pintype "passive"))
      (node (ref "U1") (pin "34") (pinfunction "P211_34") (pintype "passive"))
    )
    (net (code "47") (name "/P212{slash}EXTAL") (class "Default")
      (node (ref "C14") (pin "2") (pinfunction "2_2") (pintype "passive"))
      (node (ref "J2") (pin "10") (pinfunction "10_10") (pintype "passive"))
      (node (ref "U1") (pin "14") (pinfunction "P212/EXTAL_14") (pintype "passive"))
      (node (ref "X1") (pin "3") (pinfunction "2_3") (pintype "passive"))
    )
    (net (code "48") (name "/P213{slash}XTAL") (class "Default")
      (node (ref "C13") (pin "2") (pinfunction "2_2") (pintype "passive"))
      (node (ref "J2") (pin "11") (pinfunction "11_11") (pintype "passive"))
      (node (ref "U1") (pin "13") (pinfunction "P213/XTAL_13") (pintype "passive"))
      (node (ref "X1") (pin "1") (pinfunction "1_1") (pintype "passive"))
    )
    (net (code "49") (name "/P214") (class "Default")
      (node (ref "J4") (pin "31") (pinfunction "31_31") (pintype "passive"))
      (node (ref "U1") (pin "33") (pinfunction "P214_33") (pintype "passive"))
    )
    (net (code "50") (name "/P300{slash}TCK{slash}SWCLK") (class "Default")
      (node (ref "J1") (pin "16") (pinfunction "16_16") (pintype "passive"))
      (node (ref "J10") (pin "4") (pinfunction "4_4") (pintype "passive"))
      (node (ref "R12") (pin "1") (pinfunction "1_1") (pintype "passive"))
      (node (ref "U1") (pin "50") (pinfunction "P300/TCK/SWCLK_50") (pintype "passive"))
    )
    (net (code "51") (name "/P301") (class "Default")
      (node (ref "J1") (pin "13") (pinfunction "13_13") (pintype "passive"))
      (node (ref "U1") (pin "49") (pinfunction "P301_49") (pintype "passive"))
    )
    (net (code "52") (name "/P302") (class "Default")
      (node (ref "J1") (pin "6") (pinfunction "6_6") (pintype "passive"))
      (node (ref "U1") (pin "48") (pinfunction "P302_48") (pintype "passive"))
    )
    (net (code "53") (name "/P303") (class "Default")
      (node (ref "J3") (pin "7") (pinfunction "7_7") (pintype "passive"))
      (node (ref "U1") (pin "47") (pinfunction "P303_47") (pintype "passive"))
    )
    (net (code "54") (name "/P304") (class "Default")
      (node (ref "J3") (pin "35") (pinfunction "35_35") (pintype "passive"))
      (node (ref "J5") (pin "7") (pinfunction "7_7") (pintype "passive"))
      (node (ref "U1") (pin "44") (pinfunction "P304_44") (pintype "passive"))
    )
    (net (code "55") (name "/P305") (class "Default")
      (node (ref "J3") (pin "6") (pinfunction "6_6") (pintype "passive"))
      (node (ref "U1") (pin "43") (pinfunction "P305_43") (pintype "passive"))
    )
    (net (code "56") (name "/P306") (class "Default")
      (node (ref "J3") (pin "36") (pinfunction "36_36") (pintype "passive"))
      (node (ref "U1") (pin "42") (pinfunction "P306_42") (pintype "passive"))
    )
    (net (code "57") (name "/P307") (class "Default")
      (node (ref "J3") (pin "5") (pinfunction "5_5") (pintype "passive"))
      (node (ref "U1") (pin "41") (pinfunction "P307_41") (pintype "passive"))
    )
    (net (code "58") (name "/P400") (class "Default")
      (node (ref "J1") (pin "1") (pinfunction "1_1") (pintype "passive"))
      (node (ref "U1") (pin "1") (pinfunction "P400_1") (pintype "passive"))
    )
    (net (code "59") (name "/P401") (class "Default")
      (node (ref "J1") (pin "2") (pinfunction "2_2") (pintype "passive"))
      (node (ref "U1") (pin "2") (pinfunction "P401_2") (pintype "passive"))
    )
    (net (code "60") (name "/P402") (class "Default")
      (node (ref "J1") (pin "36") (pinfunction "36_36") (pintype "passive"))
      (node (ref "J5") (pin "9") (pinfunction "9_9") (pintype "passive"))
      (node (ref "U1") (pin "3") (pinfunction "P402_3") (pintype "passive"))
    )
    (net (code "61") (name "/P403") (class "Default")
      (node (ref "J1") (pin "17") (pinfunction "17_17") (pintype "passive"))
      (node (ref "U1") (pin "4") (pinfunction "P403_4") (pintype "passive"))
    )
    (net (code "62") (name "/P404") (class "Default")
      (node (ref "J1") (pin "34") (pinfunction "34_34") (pintype "passive"))
      (node (ref "J5") (pin "8") (pinfunction "8_8") (pintype "passive"))
      (node (ref "U1") (pin "5") (pinfunction "P404_5") (pintype "passive"))
    )
    (net (code "63") (name "/P405") (class "Default")
      (node (ref "J1") (pin "33") (pinfunction "33_33") (pintype "passive"))
      (node (ref "J5") (pin "10") (pinfunction "10_10") (pintype "passive"))
      (node (ref "U1") (pin "6") (pinfunction "P405_6") (pintype "passive"))
    )
    (net (code "64") (name "/P406") (class "Default")
      (node (ref "J1") (pin "32") (pinfunction "32_32") (pintype "passive"))
      (node (ref "U1") (pin "7") (pinfunction "P406_7") (pintype "passive"))
    )
    (net (code "65") (name "/P407") (class "Default")
      (node (ref "C22") (pin "1") (pinfunction "1_1") (pintype "passive"))
      (node (ref "J2") (pin "30") (pinfunction "30_30") (pintype "passive"))
      (node (ref "RA1") (pin "1") (pinfunction "1_1") (pintype "passive"))
      (node (ref "RA1") (pin "2") (pinfunction "2_2") (pintype "passive"))
      (node (ref "RA1") (pin "3") (pinfunction "3_3") (pintype "passive"))
      (node (ref "U1") (pin "25") (pinfunction "P407_25") (pintype "passive"))
    )
    (net (code "66") (name "/P408") (class "Default")
      (node (ref "J2") (pin "33") (pinfunction "33_33") (pintype "passive"))
      (node (ref "U1") (pin "24") (pinfunction "P408_24") (pintype "passive"))
    )
    (net (code "67") (name "/P409") (class "Default")
      (node (ref "J2") (pin "32") (pinfunction "32_32") (pintype "passive"))
      (node (ref "U1") (pin "23") (pinfunction "P409_23") (pintype "passive"))
    )
    (net (code "68") (name "/P410") (class "Default")
      (node (ref "J4") (pin "34") (pinfunction "34_34") (pintype "passive"))
      (node (ref "U1") (pin "22") (pinfunction "P410_22") (pintype "passive"))
    )
    (net (code "69") (name "/P411") (class "Default")
      (node (ref "J2") (pin "31") (pinfunction "31_31") (pintype "passive"))
      (node (ref "U1") (pin "21") (pinfunction "P411_21") (pintype "passive"))
    )
    (net (code "70") (name "/P412") (class "Default")
      (node (ref "J2") (pin "1") (pinfunction "1_1") (pintype "passive"))
      (node (ref "U1") (pin "20") (pinfunction "P412_20") (pintype "passive"))
    )
    (net (code "71") (name "/P413") (class "Default")
      (node (ref "J2") (pin "2") (pinfunction "2_2") (pintype "passive"))
      (node (ref "U1") (pin "19") (pinfunction "P413_19") (pintype "passive"))
    )
    (net (code "72") (name "/P414") (class "Default")
      (node (ref "J1") (pin "18") (pinfunction "18_18") (pintype "passive"))
      (node (ref "U1") (pin "18") (pinfunction "P414_18") (pintype "passive"))
    )
    (net (code "73") (name "/P415") (class "Default")
      (node (ref "J2") (pin "3") (pinfunction "3_3") (pintype "passive"))
      (node (ref "R3") (pin "1") (pinfunction "1_1") (pintype "passive"))
      (node (ref "S1") (pin "1") (pinfunction "1_1") (pintype "passive"))
      (node (ref "S1") (pin "3") (pinfunction "3_3") (pintype "passive"))
      (node (ref "U1") (pin "17") (pinfunction "P415_17") (pintype "passive"))
    )
    (net (code "74") (name "/P500") (class "Default")
      (node (ref "J4") (pin "1") (pinfunction "1_1") (pintype "passive"))
      (node (ref "U1") (pin "76") (pinfunction "P500_76") (pintype "passive"))
    )
    (net (code "75") (name "/P501") (class "Default")
      (node (ref "J4") (pin "2") (pinfunction "2_2") (pintype "passive"))
      (node (ref "U1") (pin "77") (pinfunction "P501_77") (pintype "passive"))
    )
    (net (code "76") (name "/P502") (class "Default")
      (node (ref "J4") (pin "3") (pinfunction "3_3") (pintype "passive"))
      (node (ref "U1") (pin "78") (pinfunction "P502_78") (pintype "passive"))
    )
    (net (code "77") (name "/P503") (class "Default")
      (node (ref "J4") (pin "4") (pinfunction "4_4") (pintype "passive"))
      (node (ref "U1") (pin "79") (pinfunction "P503_79") (pintype "passive"))
    )
    (net (code "78") (name "/P504") (class "Default")
      (node (ref "J4") (pin "5") (pinfunction "5_5") (pintype "passive"))
      (node (ref "U1") (pin "80") (pinfunction "P504_80") (pintype "passive"))
    )
    (net (code "79") (name "/P508") (class "Default")
      (node (ref "J4") (pin "6") (pinfunction "6_6") (pintype "passive"))
      (node (ref "U1") (pin "81") (pinfunction "P508_81") (pintype "passive"))
    )
    (net (code "80") (name "/P600") (class "Default")
      (node (ref "J1") (pin "12") (pinfunction "12_12") (pintype "passive"))
      (node (ref "U1") (pin "67") (pinfunction "P600_67") (pintype "passive"))
    )
    (net (code "81") (name "/P601") (class "Default")
      (node (ref "J1") (pin "10") (pinfunction "10_10") (pintype "passive"))
      (node (ref "U1") (pin "66") (pinfunction "P601_66") (pintype "passive"))
    )
    (net (code "82") (name "/P602") (class "Default")
      (node (ref "J1") (pin "11") (pinfunction "11_11") (pintype "passive"))
      (node (ref "U1") (pin "65") (pinfunction "P602_65") (pintype "passive"))
    )
    (net (code "83") (name "/P608") (class "Default")
      (node (ref "J3") (pin "10") (pinfunction "10_10") (pintype "passive"))
      (node (ref "U1") (pin "59") (pinfunction "P608_59") (pintype "passive"))
    )
    (net (code "84") (name "/P609") (class "Default")
      (node (ref "J1") (pin "15") (pinfunction "15_15") (pintype "passive"))
      (node (ref "U1") (pin "60") (pinfunction "P609_60") (pintype "passive"))
    )
    (net (code "85") (name "/P610") (class "Default")
      (node (ref "J1") (pin "14") (pinfunction "14_14") (pintype "passive"))
      (node (ref "U1") (pin "61") (pinfunction "P610_61") (pintype "passive"))
    )
    (net (code "86") (name "/P708") (class "Default")
      (node (ref "J2") (pin "4") (pinfunction "4_4") (pintype "passive"))
      (node (ref "U1") (pin "16") (pinfunction "P708_16") (pintype "passive"))
    )
    (net (code "87") (name "/RES") (class "Default")
      (node (ref "J1") (pin "24") (pinfunction "24_24") (pintype "passive"))
      (node (ref "J10") (pin "10") (pinfunction "10_10") (pintype "passive"))
      (node (ref "R6") (pin "1") (pinfunction "1_1") (pintype "passive"))
      (node (ref "S2") (pin "1") (pinfunction "1_1") (pintype "passive"))
      (node (ref "S2") (pin "3") (pinfunction "3_3") (pintype "passive"))
      (node (ref "U1") (pin "38") (pinfunction "RES_38") (pintype "passive"))
      (node (ref "U2") (pin "46") (pinfunction "P102_46") (pintype "passive"))
    )
    (net (code "88") (name "/TS_CONN") (class "Default")
      (node (ref "C33") (pin "2") (pinfunction "2_2") (pintype "passive"))
      (node (ref "R4") (pin "2") (pinfunction "2_2") (pintype "passive"))
      (node (ref "TS1") (pin "2") (pinfunction "2_2") (pintype "passive"))
    )
    (net (code "89") (name "/USBMCU_N") (class "Default")
      (node (ref "FL1") (pin "1") (pinfunction "1_1") (pintype "passive"))
      (node (ref "J1") (pin "40") (pinfunction "40_40") (pintype "passive"))
      (node (ref "U1") (pin "27") (pinfunction "USB_DM_27") (pintype "passive"))
    )
    (net (code "90") (name "/USBMCU_P") (class "Default")
      (node (ref "FL1") (pin "4") (pinfunction "4_4") (pintype "passive"))
      (node (ref "J1") (pin "39") (pinfunction "39_39") (pintype "passive"))
      (node (ref "U1") (pin "28") (pinfunction "USB_DP_28") (pintype "passive"))
    )
    (net (code "91") (name "/VCL") (class "Default")
      (node (ref "C51") (pin "2") (pinfunction "2_2") (pintype "passive"))
      (node (ref "J3") (pin "26") (pinfunction "26_26") (pintype "passive"))
      (node (ref "U1") (pin "64") (pinfunction "VCL_64") (pintype "passive"))
    )
    (net (code "92") (name "/VCL0") (class "Default")
      (node (ref "C17") (pin "2") (pinfunction "2_2") (pintype "passive"))
      (node (ref "J2") (pin "14") (pinfunction "14_14") (pintype "passive"))
      (node (ref "U1") (pin "9") (pinfunction "VCL0_9") (pintype "passive"))
    )
    (net (code "93") (name "/XCIN") (class "Default")
      (node (ref "C15") (pin "1") (pinfunction "1_1") (pintype "passive"))
      (node (ref "J2") (pin "13") (pinfunction "13_13") (pintype "passive"))
      (node (ref "U1") (pin "10") (pinfunction "XCIN_10") (pintype "passive"))
      (node (ref "X2") (pin "1") (pinfunction "1_1") (pintype "passive"))
    )
    (net (code "94") (name "/XOUT") (class "Default")
      (node (ref "C16") (pin "1") (pinfunction "1_1") (pintype "passive"))
      (node (ref "U1") (pin "11") (pinfunction "XCOUT_11") (pintype "passive"))
      (node (ref "X2") (pin "2") (pinfunction "2_2") (pintype "passive"))
    )
    (net (code "95") (name "3V3") (class "Default")
      (node (ref "C19") (pin "2") (pinfunction "2_2") (pintype "passive"))
      (node (ref "C20") (pin "2") (pinfunction "2_2") (pintype "passive"))
      (node (ref "C24") (pin "2") (pinfunction "2_2") (pintype "passive"))
      (node (ref "C25") (pin "2") (pinfunction "2_2") (pintype "passive"))
      (node (ref "C27") (pin "2") (pinfunction "2_2") (pintype "passive"))
      (node (ref "C29") (pin "2") (pinfunction "2_2") (pintype "passive"))
      (node (ref "C3") (pin "1") (pinfunction "1_1") (pintype "passive"))
      (node (ref "C5") (pin "2") (pinfunction "2_2") (pintype "passive"))
      (node (ref "J10") (pin "1") (pinfunction "1_1") (pintype "passive"))
      (node (ref "J12") (pin "1") (pinfunction "1_1") (pintype "passive"))
      (node (ref "J2") (pin "15") (pinfunction "15_15") (pintype "passive"))
      (node (ref "J5") (pin "12") (pinfunction "12_12") (pintype "passive"))
      (node (ref "J6") (pin "6") (pinfunction "6_6") (pintype "passive"))
      (node (ref "POT1") (pin "1") (pinfunction "CCW_1") (pintype "passive"))
      (node (ref "R1") (pin "1") (pinfunction "1_1") (pintype "passive"))
      (node (ref "R10") (pin "2") (pinfunction "2_2") (pintype "passive"))
      (node (ref "U1") (pin "8") (pinfunction "VBATT_8") (pintype "passive"))
      (node (ref "U2") (pin "20") (pinfunction "VCC_USB_20") (pintype "passive"))
      (node (ref "U2") (pin "39") (pinfunction "VCC_2_39") (pintype "passive"))
      (node (ref "U3") (pin "3") (pinfunction "VROUT_3") (pintype "power_in"))
    )
    (net (code "96") (name "3V3MCU") (class "Default")
      (node (ref "C11") (pin "2") (pinfunction "2_2") (pintype "passive"))
      (node (ref "C18") (pin "2") (pinfunction "2_2") (pintype "passive"))
      (node (ref "C21") (pin "2") (pinfunction "2_2") (pintype "passive"))
      (node (ref "C23") (pin "2") (pinfunction "2_2") (pintype "passive"))
      (node (ref "C4") (pin "2") (pinfunction "2_2") (pintype "passive"))
      (node (ref "C50") (pin "2") (pinfunction "2_2") (pintype "passive"))
      (node (ref "C53") (pin "2") (pinfunction "2_2") (pintype "passive"))
      (node (ref "C7") (pin "2") (pinfunction "2_2") (pintype "passive"))
      (node (ref "C8") (pin "2") (pinfunction "2_2") (pintype "passive"))
      (node (ref "J1") (pin "38") (pinfunction "38_38") (pintype "passive"))
      (node (ref "J1") (pin "8") (pinfunction "8_8") (pintype "passive"))
      (node (ref "J2") (pin "22") (pinfunction "22_22") (pintype "passive"))
      (node (ref "J2") (pin "25") (pinfunction "25_25") (pintype "passive"))
      (node (ref "J2") (pin "36") (pinfunction "36_36") (pintype "passive"))
      (node (ref "J4") (pin "14") (pinfunction "14_14") (pintype "passive"))
      (node (ref "J4") (pin "19") (pinfunction "19_19") (pintype "passive"))
      (node (ref "R3") (pin "2") (pinfunction "2_2") (pintype "passive"))
      (node (ref "R6") (pin "2") (pinfunction "2_2") (pintype "passive"))
      (node (ref "R7") (pin "2") (pinfunction "2_2") (pintype "passive"))
      (node (ref "R8") (pin "2") (pinfunction "2_2") (pintype "passive"))
      (node (ref "U1") (pin "15") (pinfunction "VCC_1_15") (pintype "passive"))
      (node (ref "U1") (pin "29") (pinfunction "VCC_USB_29") (pintype "passive"))
      (node (ref "U1") (pin "46") (pinfunction "VCC_2_46") (pintype "passive"))
      (node (ref "U1") (pin "62") (pinfunction "VCC_3_62") (pintype "passive"))
      (node (ref "U1") (pin "82") (pinfunction "VCC_4_82") (pintype "passive"))
      (node (ref "U1") (pin "87") (pinfunction "VREFH_87") (pintype "passive"))
      (node (ref "U1") (pin "88") (pinfunction "AVCC0_88") (pintype "passive"))
      (node (ref "U1") (pin "91") (pinfunction "VREFH0_91") (pintype "passive"))
      (node (ref "U2") (pin "56") (pinfunction "AVCC0_56") (pintype "passive"))
    )
    (net (code "97") (name "GND") (class "Default")
      (node (ref "C1") (pin "1") (pinfunction "1_1") (pintype "passive"))
      (node (ref "C11") (pin "1") (pinfunction "1_1") (pintype "passive"))
      (node (ref "C12") (pin "2") (pinfunction "2_2") (pintype "passive"))
      (node (ref "C13") (pin "1") (pinfunction "1_1") (pintype "passive"))
      (node (ref "C14") (pin "1") (pinfunction "1_1") (pintype "passive"))
      (node (ref "C15") (pin "2") (pinfunction "2_2") (pintype "passive"))
      (node (ref "C16") (pin "2") (pinfunction "2_2") (pintype "passive"))
      (node (ref "C17") (pin "1") (pinfunction "1_1") (pintype "passive"))
      (node (ref "C18") (pin "1") (pinfunction "1_1") (pintype "passive"))
      (node (ref "C19") (pin "1") (pinfunction "1_1") (pintype "passive"))
      (node (ref "C2") (pin "2") (pinfunction "2_2") (pintype "passive"))
      (node (ref "C20") (pin "1") (pinfunction "1_1") (pintype "passive"))
      (node (ref "C21") (pin "1") (pinfunction "1_1") (pintype "passive"))
      (node (ref "C22") (pin "2") (pinfunction "2_2") (pintype "passive"))
      (node (ref "C23") (pin "1") (pinfunction "1_1") (pintype "passive"))
      (node (ref "C24") (pin "1") (pinfunction "1_1") (pintype "passive"))
      (node (ref "C25") (pin "1") (pinfunction "1_1") (pintype "passive"))
      (node (ref "C26") (pin "1") (pinfunction "1_1") (pintype "passive"))
      (node (ref "C27") (pin "1") (pinfunction "1_1") (pintype "passive"))
      (node (ref "C28") (pin "2") (pinfunction "2_2") (pintype "passive"))
      (node (ref "C29") (pin "1") (pinfunction "1_1") (pintype "passive"))
      (node (ref "C3") (pin "2") (pinfunction "2_2") (pintype "passive"))
      (node (ref "C30") (pin "1") (pinfunction "1_1") (pintype "passive"))
      (node (ref "C31") (pin "2") (pinfunction "2_2") (pintype "passive"))
      (node (ref "C32") (pin "2") (pinfunction "2_2") (pintype "passive"))
      (node (ref "C33") (pin "1") (pinfunction "1_1") (pintype "passive"))
      (node (ref "C4") (pin "1") (pinfunction "1_1") (pintype "passive"))
      (node (ref "C5") (pin "1") (pinfunction "1_1") (pintype "passive"))
      (node (ref "C50") (pin "1") (pinfunction "1_1") (pintype "passive"))
      (node (ref "C51") (pin "1") (pinfunction "1_1") (pintype "passive"))
      (node (ref "C53") (pin "1") (pinfunction "1_1") (pintype "passive"))
      (node (ref "C7") (pin "1") (pinfunction "1_1") (pintype "passive"))
      (node (ref "C8") (pin "1") (pinfunction "1_1") (pintype "passive"))
      (node (ref "J1") (pin "9") (pinfunction "9_9") (pintype "passive"))
      (node (ref "J10") (pin "3") (pinfunction "3_3") (pintype "passive"))
      (node (ref "J10") (pin "5") (pinfunction "5_5") (pintype "passive"))
      (node (ref "J10") (pin "9") (pinfunction "9_9") (pintype "passive"))
      (node (ref "J11") (pin "5") (pinfunction "GND_5") (pintype "passive"))
      (node (ref "J12") (pin "5") (pinfunction "5_5") (pintype "passive"))
      (node (ref "J2") (pin "23") (pinfunction "23_23") (pintype "passive"))
      (node (ref "J2") (pin "24") (pinfunction "24_24") (pintype "passive"))
      (node (ref "J2") (pin "35") (pinfunction "35_35") (pintype "passive"))
      (node (ref "J4") (pin "23") (pinfunction "23_23") (pintype "passive"))
      (node (ref "J4") (pin "27") (pinfunction "27_27") (pintype "passive"))
      (node (ref "J5") (pin "11") (pinfunction "11_11") (pintype "passive"))
      (node (ref "J5") (pin "5") (pinfunction "5_5") (pintype "passive"))
      (node (ref "J5") (pin "6") (pinfunction "6_6") (pintype "passive"))
      (node (ref "J6") (pin "5") (pinfunction "5_5") (pintype "passive"))
      (node (ref "J9") (pin "4") (pinfunction "ID_4") (pintype "passive"))
      (node (ref "J9") (pin "5") (pinfunction "GND_5") (pintype "passive"))
      (node (ref "LED1") (pin "1") (pinfunction "K2_1") (pintype "passive"))
      (node (ref "LED2") (pin "2") (pinfunction "K_YG_2") (pintype "passive"))
      (node (ref "LED2") (pin "4") (pinfunction "K_R_4") (pintype "passive"))
      (node (ref "POT1") (pin "3") (pinfunction "CW_3") (pintype "passive"))
      (node (ref "R9") (pin "1") (pinfunction "1_1") (pintype "passive"))
      (node (ref "RA1") (pin "5") (pinfunction "5_5") (pintype "passive"))
      (node (ref "RA1") (pin "6") (pinfunction "6_6") (pintype "passive"))
      (node (ref "RA2") (pin "7") (pinfunction "7_7") (pintype "passive"))
      (node (ref "RA2") (pin "8") (pinfunction "8_8") (pintype "passive"))
      (node (ref "S1") (pin "2") (pinfunction "2_2") (pintype "passive"))
      (node (ref "S1") (pin "4") (pinfunction "4_4") (pintype "passive"))
      (node (ref "S2") (pin "2") (pinfunction "2_2") (pintype "passive"))
      (node (ref "S2") (pin "4") (pinfunction "4_4") (pintype "passive"))
      (node (ref "U1") (pin "12") (pinfunction "VSS_1_12") (pintype "passive"))
      (node (ref "U1") (pin "26") (pinfunction "VSS_USB_26") (pintype "passive"))
      (node (ref "U1") (pin "45") (pinfunction "VSS_2_45") (pintype "passive"))
      (node (ref "U1") (pin "63") (pinfunction "VSS_3_63") (pintype "passive"))
      (node (ref "U1") (pin "83") (pinfunction "VSS_4_83") (pintype "passive"))
      (node (ref "U1") (pin "86") (pinfunction "VREFL_86") (pintype "passive"))
      (node (ref "U1") (pin "89") (pinfunction "AVSS0_89") (pintype "passive"))
      (node (ref "U1") (pin "90") (pinfunction "VREFL0_90") (pintype "passive"))
      (node (ref "U2") (pin "17") (pinfunction "VSS_USB_17") (pintype "passive"))
      (node (ref "U2") (pin "40") (pinfunction "VSS_2_40") (pintype "passive"))
      (node (ref "U2") (pin "57") (pinfunction "AVSS0_57") (pintype "passive"))
      (node (ref "U2") (pin "8") (pinfunction "VSS_1_8") (pintype "passive"))
      (node (ref "U3") (pin "1") (pinfunction "GND_1") (pintype "power_in"))
      (node (ref "X1") (pin "2") (pinfunction "GND_2") (pintype "power_in"))
      (node (ref "X1") (pin "4") (pinfunction "GND_4") (pintype "power_in"))
    )
    (net (code "98") (name "Net-(C31-Pad1)") (class "Default")
      (node (ref "C31") (pin "1") (pinfunction "1_1") (pintype "passive"))
      (node (ref "FL1") (pin "2") (pinfunction "2_2") (pintype "passive"))
      (node (ref "R51") (pin "1") (pinfunction "1_1") (pintype "passive"))
    )
    (net (code "99") (name "Net-(C32-Pad1)") (class "Default")
      (node (ref "C32") (pin "1") (pinfunction "1_1") (pintype "passive"))
      (node (ref "FL1") (pin "3") (pinfunction "3_3") (pintype "passive"))
      (node (ref "R52") (pin "1") (pinfunction "1_1") (pintype "passive"))
    )
    (net (code "100") (name "Net-(D1-K)") (class "Default")
      (node (ref "C1") (pin "2") (pinfunction "2_2") (pintype "passive"))
      (node (ref "C2") (pin "1") (pinfunction "1_1") (pintype "passive"))
      (node (ref "D1") (pin "1") (pinfunction "K_1") (pintype "passive"))
      (node (ref "U3") (pin "2") (pinfunction "VIN_2") (pintype "power_in"))
    )
    (net (code "101") (name "Net-(J8-Pad2)") (class "Default")
      (node (ref "J8") (pin "2") (pinfunction "2_2") (pintype "passive"))
      (node (ref "R8") (pin "1") (pinfunction "1_1") (pintype "passive"))
    )
    (net (code "102") (name "Net-(J8-Pad3)") (class "Default")
      (node (ref "J8") (pin "3") (pinfunction "3_3") (pintype "passive"))
      (node (ref "R9") (pin "2") (pinfunction "2_2") (pintype "passive"))
    )
    (net (code "103") (name "Net-(J9-D+{slash}DP)") (class "Default")
      (node (ref "J9") (pin "3") (pinfunction "D+/DP_3") (pintype "passive"))
      (node (ref "R52") (pin "2") (pinfunction "2_2") (pintype "passive"))
    )
    (net (code "104") (name "Net-(J9-D-{slash}DM)") (class "Default")
      (node (ref "J9") (pin "2") (pinfunction "D-/DM_2") (pintype "passive"))
      (node (ref "R51") (pin "2") (pinfunction "2_2") (pintype "passive"))
    )
    (net (code "105") (name "Net-(J9-VBUS)") (class "Default")
      (node (ref "J9") (pin "1") (pinfunction "VBUS_1") (pintype "passive"))
      (node (ref "RA1") (pin "7") (pinfunction "7_7") (pintype "passive"))
      (node (ref "RA1") (pin "8") (pinfunction "8_8") (pintype "passive"))
    )
    (net (code "106") (name "Net-(LED1-A2)") (class "Default")
      (node (ref "LED1") (pin "2") (pinfunction "A2_2") (pintype "passive"))
      (node (ref "R5") (pin "2") (pinfunction "2_2") (pintype "passive"))
    )
    (net (code "107") (name "Net-(LED2-A_R)") (class "Default")
      (node (ref "LED2") (pin "3") (pinfunction "A_R_3") (pintype "passive"))
      (node (ref "R2") (pin "2") (pinfunction "2_2") (pintype "passive"))
    )
    (net (code "108") (name "Net-(LED2-A_YG)") (class "Default")
      (node (ref "LED2") (pin "1") (pinfunction "A_YG_1") (pintype "passive"))
      (node (ref "R1") (pin "2") (pinfunction "2_2") (pintype "passive"))
    )
    (net (code "109") (name "Net-(U2-P000)") (class "Default")
      (node (ref "R12") (pin "2") (pinfunction "2_2") (pintype "passive"))
      (node (ref "U2") (pin "64") (pinfunction "P000_64") (pintype "passive"))
    )
    (net (code "110") (name "Net-(U2-P100)") (class "Default")
      (node (ref "R11") (pin "1") (pinfunction "1_1") (pintype "passive"))
      (node (ref "U2") (pin "48") (pinfunction "P100_48") (pintype "passive"))
    )
    (net (code "111") (name "unconnected-(J1-Pad21)") (class "Default")
      (node (ref "J1") (pin "21") (pinfunction "21_21") (pintype "passive+no_connect"))
    )
    (net (code "112") (name "unconnected-(J1-Pad25)") (class "Default")
      (node (ref "J1") (pin "25") (pinfunction "25_25") (pintype "passive+no_connect"))
    )
    (net (code "113") (name "unconnected-(J1-Pad26)") (class "Default")
      (node (ref "J1") (pin "26") (pinfunction "26_26") (pintype "passive+no_connect"))
    )
    (net (code "114") (name "unconnected-(J1-Pad27)") (class "Default")
      (node (ref "J1") (pin "27") (pinfunction "27_27") (pintype "passive+no_connect"))
    )
    (net (code "115") (name "unconnected-(J1-Pad28)") (class "Default")
      (node (ref "J1") (pin "28") (pinfunction "28_28") (pintype "passive+no_connect"))
    )
    (net (code "116") (name "unconnected-(J1-Pad29)") (class "Default")
      (node (ref "J1") (pin "29") (pinfunction "29_29") (pintype "passive+no_connect"))
    )
    (net (code "117") (name "unconnected-(J1-Pad30)") (class "Default")
      (node (ref "J1") (pin "30") (pinfunction "30_30") (pintype "passive+no_connect"))
    )
    (net (code "118") (name "unconnected-(J1-Pad31)") (class "Default")
      (node (ref "J1") (pin "31") (pinfunction "31_31") (pintype "passive+no_connect"))
    )
    (net (code "119") (name "unconnected-(J1-Pad35)") (class "Default")
      (node (ref "J1") (pin "35") (pinfunction "35_35") (pintype "passive+no_connect"))
    )
    (net (code "120") (name "unconnected-(J2-Pad5)") (class "Default")
      (node (ref "J2") (pin "5") (pinfunction "5_5") (pintype "passive+no_connect"))
    )
    (net (code "121") (name "unconnected-(J2-Pad6)") (class "Default")
      (node (ref "J2") (pin "6") (pinfunction "6_6") (pintype "passive+no_connect"))
    )
    (net (code "122") (name "unconnected-(J2-Pad7)") (class "Default")
      (node (ref "J2") (pin "7") (pinfunction "7_7") (pintype "passive+no_connect"))
    )
    (net (code "123") (name "unconnected-(J2-Pad8)") (class "Default")
      (node (ref "J2") (pin "8") (pinfunction "8_8") (pintype "passive+no_connect"))
    )
    (net (code "124") (name "unconnected-(J2-Pad9)") (class "Default")
      (node (ref "J2") (pin "9") (pinfunction "9_9") (pintype "passive+no_connect"))
    )
    (net (code "125") (name "unconnected-(J2-Pad12)") (class "Default")
      (node (ref "J2") (pin "12") (pinfunction "12_12") (pintype "passive"))
    )
    (net (code "126") (name "unconnected-(J2-Pad16)") (class "Default")
      (node (ref "J2") (pin "16") (pinfunction "16_16") (pintype "passive+no_connect"))
    )
    (net (code "127") (name "unconnected-(J2-Pad17)") (class "Default")
      (node (ref "J2") (pin "17") (pinfunction "17_17") (pintype "passive+no_connect"))
    )
    (net (code "128") (name "unconnected-(J2-Pad18)") (class "Default")
      (node (ref "J2") (pin "18") (pinfunction "18_18") (pintype "passive+no_connect"))
    )
    (net (code "129") (name "unconnected-(J2-Pad19)") (class "Default")
      (node (ref "J2") (pin "19") (pinfunction "19_19") (pintype "passive+no_connect"))
    )
    (net (code "130") (name "unconnected-(J2-Pad20)") (class "Default")
      (node (ref "J2") (pin "20") (pinfunction "20_20") (pintype "passive+no_connect"))
    )
    (net (code "131") (name "unconnected-(J3-Pad1)") (class "Default")
      (node (ref "J3") (pin "1") (pinfunction "1_1") (pintype "passive+no_connect"))
    )
    (net (code "132") (name "unconnected-(J3-Pad2)") (class "Default")
      (node (ref "J3") (pin "2") (pinfunction "2_2") (pintype "passive+no_connect"))
    )
    (net (code "133") (name "unconnected-(J3-Pad3)") (class "Default")
      (node (ref "J3") (pin "3") (pinfunction "3_3") (pintype "passive+no_connect"))
    )
    (net (code "134") (name "unconnected-(J3-Pad4)") (class "Default")
      (node (ref "J3") (pin "4") (pinfunction "4_4") (pintype "passive+no_connect"))
    )
    (net (code "135") (name "unconnected-(J3-Pad11)") (class "Default")
      (node (ref "J3") (pin "11") (pinfunction "11_11") (pintype "passive+no_connect"))
    )
    (net (code "136") (name "unconnected-(J3-Pad12)") (class "Default")
      (node (ref "J3") (pin "12") (pinfunction "12_12") (pintype "passive+no_connect"))
    )
    (net (code "137") (name "unconnected-(J3-Pad13)") (class "Default")
      (node (ref "J3") (pin "13") (pinfunction "13_13") (pintype "passive+no_connect"))
    )
    (net (code "138") (name "unconnected-(J3-Pad14)") (class "Default")
      (node (ref "J3") (pin "14") (pinfunction "14_14") (pintype "passive+no_connect"))
    )
    (net (code "139") (name "unconnected-(J3-Pad15)") (class "Default")
      (node (ref "J3") (pin "15") (pinfunction "15_15") (pintype "passive+no_connect"))
    )
    (net (code "140") (name "unconnected-(J3-Pad16)") (class "Default")
      (node (ref "J3") (pin "16") (pinfunction "16_16") (pintype "passive+no_connect"))
    )
    (net (code "141") (name "unconnected-(J3-Pad17)") (class "Default")
      (node (ref "J3") (pin "17") (pinfunction "17_17") (pintype "passive+no_connect"))
    )
    (net (code "142") (name "unconnected-(J3-Pad18)") (class "Default")
      (node (ref "J3") (pin "18") (pinfunction "18_18") (pintype "passive+no_connect"))
    )
    (net (code "143") (name "unconnected-(J3-Pad21)") (class "Default")
      (node (ref "J3") (pin "21") (pinfunction "21_21") (pintype "passive+no_connect"))
    )
    (net (code "144") (name "unconnected-(J3-Pad23)") (class "Default")
      (node (ref "J3") (pin "23") (pinfunction "23_23") (pintype "passive+no_connect"))
    )
    (net (code "145") (name "unconnected-(J3-Pad24)") (class "Default")
      (node (ref "J3") (pin "24") (pinfunction "24_24") (pintype "passive+no_connect"))
    )
    (net (code "146") (name "unconnected-(J3-Pad25)") (class "Default")
      (node (ref "J3") (pin "25") (pinfunction "25_25") (pintype "passive+no_connect"))
    )
    (net (code "147") (name "unconnected-(J3-Pad27)") (class "Default")
      (node (ref "J3") (pin "27") (pinfunction "27_27") (pintype "passive+no_connect"))
    )
    (net (code "148") (name "unconnected-(J3-Pad28)") (class "Default")
      (node (ref "J3") (pin "28") (pinfunction "28_28") (pintype "passive+no_connect"))
    )
    (net (code "149") (name "unconnected-(J3-Pad29)") (class "Default")
      (node (ref "J3") (pin "29") (pinfunction "29_29") (pintype "passive+no_connect"))
    )
    (net (code "150") (name "unconnected-(J3-Pad30)") (class "Default")
      (node (ref "J3") (pin "30") (pinfunction "30_30") (pintype "passive+no_connect"))
    )
    (net (code "151") (name "unconnected-(J3-Pad31)") (class "Default")
      (node (ref "J3") (pin "31") (pinfunction "31_31") (pintype "passive+no_connect"))
    )
    (net (code "152") (name "unconnected-(J3-Pad34)") (class "Default")
      (node (ref "J3") (pin "34") (pinfunction "34_34") (pintype "passive+no_connect"))
    )
    (net (code "153") (name "unconnected-(J3-Pad37)") (class "Default")
      (node (ref "J3") (pin "37") (pinfunction "37_37") (pintype "passive+no_connect"))
    )
    (net (code "154") (name "unconnected-(J3-Pad38)") (class "Default")
      (node (ref "J3") (pin "38") (pinfunction "38_38") (pintype "passive+no_connect"))
    )
    (net (code "155") (name "unconnected-(J3-Pad39)") (class "Default")
      (node (ref "J3") (pin "39") (pinfunction "39_39") (pintype "passive+no_connect"))
    )
    (net (code "156") (name "unconnected-(J3-Pad40)") (class "Default")
      (node (ref "J3") (pin "40") (pinfunction "40_40") (pintype "passive+no_connect"))
    )
    (net (code "157") (name "unconnected-(J4-Pad7)") (class "Default")
      (node (ref "J4") (pin "7") (pinfunction "7_7") (pintype "passive+no_connect"))
    )
    (net (code "158") (name "unconnected-(J4-Pad8)") (class "Default")
      (node (ref "J4") (pin "8") (pinfunction "8_8") (pintype "passive+no_connect"))
    )
    (net (code "159") (name "unconnected-(J4-Pad15)") (class "Default")
      (node (ref "J4") (pin "15") (pinfunction "15_15") (pintype "passive+no_connect"))
    )
    (net (code "160") (name "unconnected-(J4-Pad16)") (class "Default")
      (node (ref "J4") (pin "16") (pinfunction "16_16") (pintype "passive+no_connect"))
    )
    (net (code "161") (name "unconnected-(J4-Pad17)") (class "Default")
      (node (ref "J4") (pin "17") (pinfunction "17_17") (pintype "passive+no_connect"))
    )
    (net (code "162") (name "unconnected-(J4-Pad18)") (class "Default")
      (node (ref "J4") (pin "18") (pinfunction "18_18") (pintype "passive+no_connect"))
    )
    (net (code "163") (name "unconnected-(J4-Pad20)") (class "Default")
      (node (ref "J4") (pin "20") (pinfunction "20_20") (pintype "passive+no_connect"))
    )
    (net (code "164") (name "unconnected-(J4-Pad21)") (class "Default")
      (node (ref "J4") (pin "21") (pinfunction "21_21") (pintype "passive+no_connect"))
    )
    (net (code "165") (name "unconnected-(J4-Pad22)") (class "Default")
      (node (ref "J4") (pin "22") (pinfunction "22_22") (pintype "passive+no_connect"))
    )
    (net (code "166") (name "unconnected-(J4-Pad24)") (class "Default")
      (node (ref "J4") (pin "24") (pinfunction "24_24") (pintype "passive+no_connect"))
    )
    (net (code "167") (name "unconnected-(J4-Pad25)") (class "Default")
      (node (ref "J4") (pin "25") (pinfunction "25_25") (pintype "passive+no_connect"))
    )
    (net (code "168") (name "unconnected-(J4-Pad26)") (class "Default")
      (node (ref "J4") (pin "26") (pinfunction "26_26") (pintype "passive+no_connect"))
    )
    (net (code "169") (name "unconnected-(J4-Pad28)") (class "Default")
      (node (ref "J4") (pin "28") (pinfunction "28_28") (pintype "passive+no_connect"))
    )
    (net (code "170") (name "unconnected-(J4-Pad37)") (class "Default")
      (node (ref "J4") (pin "37") (pinfunction "37_37") (pintype "passive+no_connect"))
    )
    (net (code "171") (name "unconnected-(J4-Pad38)") (class "Default")
      (node (ref "J4") (pin "38") (pinfunction "38_38") (pintype "passive+no_connect"))
    )
    (net (code "172") (name "unconnected-(J4-Pad39)") (class "Default")
      (node (ref "J4") (pin "39") (pinfunction "39_39") (pintype "passive+no_connect"))
    )
    (net (code "173") (name "unconnected-(J4-Pad40)") (class "Default")
      (node (ref "J4") (pin "40") (pinfunction "40_40") (pintype "passive+no_connect"))
    )
    (net (code "174") (name "unconnected-(J8-Pad4)") (class "Default")
      (node (ref "J8") (pin "4") (pinfunction "4_4") (pintype "passive+no_connect"))
    )
    (net (code "175") (name "unconnected-(J10-Pad7)") (class "Default")
      (node (ref "J10") (pin "7") (pinfunction "7_7") (pintype "passive+no_connect"))
    )
    (net (code "176") (name "unconnected-(J11-ID-Pad4)") (class "Default")
      (node (ref "J11") (pin "4") (pinfunction "ID_4") (pintype "passive"))
    )
    (net (code "177") (name "unconnected-(J12-Pad6)") (class "Default")
      (node (ref "J12") (pin "6") (pinfunction "6_6") (pintype "passive+no_connect"))
    )
    (net (code "178") (name "unconnected-(RA1-Pad4)") (class "Default")
      (node (ref "RA1") (pin "4") (pinfunction "4_4") (pintype "passive+no_connect"))
    )
    (net (code "179") (name "unconnected-(RA2-Pad1)") (class "Default")
      (node (ref "RA2") (pin "1") (pinfunction "1_1") (pintype "passive+no_connect"))
    )
    (net (code "180") (name "unconnected-(TS1-Pad1)") (class "Default")
      (node (ref "TS1") (pin "1") (pinfunction "1_1") (pintype "passive+no_connect"))
    )
    (net (code "181") (name "unconnected-(U2-P001-Pad63)") (class "Default")
      (node (ref "U2") (pin "63") (pinfunction "P001_63") (pintype "passive+no_connect"))
    )
    (net (code "182") (name "unconnected-(U2-P002-Pad62)") (class "Default")
      (node (ref "U2") (pin "62") (pinfunction "P002_62") (pintype "passive+no_connect"))
    )
    (net (code "183") (name "unconnected-(U2-P003-Pad61)") (class "Default")
      (node (ref "U2") (pin "61") (pinfunction "P003_61") (pintype "passive+no_connect"))
    )
    (net (code "184") (name "unconnected-(U2-P004-Pad60)") (class "Default")
      (node (ref "U2") (pin "60") (pinfunction "P004_60") (pintype "passive+no_connect"))
    )
    (net (code "185") (name "unconnected-(U2-P010{slash}VREFH0-Pad59)") (class "Default")
      (node (ref "U2") (pin "59") (pinfunction "P010/VREFH0_59") (pintype "passive+no_connect"))
    )
    (net (code "186") (name "unconnected-(U2-P011{slash}VREFL0-Pad58)") (class "Default")
      (node (ref "U2") (pin "58") (pinfunction "P011/VREFL0_58") (pintype "passive+no_connect"))
    )
    (net (code "187") (name "unconnected-(U2-P012-Pad55)") (class "Default")
      (node (ref "U2") (pin "55") (pinfunction "P012_55") (pintype "passive+no_connect"))
    )
    (net (code "188") (name "unconnected-(U2-P013-Pad54)") (class "Default")
      (node (ref "U2") (pin "54") (pinfunction "P013_54") (pintype "passive+no_connect"))
    )
    (net (code "189") (name "unconnected-(U2-P014-Pad53)") (class "Default")
      (node (ref "U2") (pin "53") (pinfunction "P014_53") (pintype "passive+no_connect"))
    )
    (net (code "190") (name "unconnected-(U2-P015-Pad52)") (class "Default")
      (node (ref "U2") (pin "52") (pinfunction "P015_52") (pintype "passive+no_connect"))
    )
    (net (code "191") (name "unconnected-(U2-P101-Pad47)") (class "Default")
      (node (ref "U2") (pin "47") (pinfunction "P101_47") (pintype "passive+no_connect"))
    )
    (net (code "192") (name "unconnected-(U2-P104-Pad44)") (class "Default")
      (node (ref "U2") (pin "44") (pinfunction "P104_44") (pintype "passive+no_connect"))
    )
    (net (code "193") (name "unconnected-(U2-P105-Pad43)") (class "Default")
      (node (ref "U2") (pin "43") (pinfunction "P105_43") (pintype "passive+no_connect"))
    )
    (net (code "194") (name "unconnected-(U2-P106-Pad42)") (class "Default")
      (node (ref "U2") (pin "42") (pinfunction "P106_42") (pintype "passive+no_connect"))
    )
    (net (code "195") (name "unconnected-(U2-P107-Pad41)") (class "Default")
      (node (ref "U2") (pin "41") (pinfunction "P107_41") (pintype "passive+no_connect"))
    )
    (net (code "196") (name "unconnected-(U2-P109-Pad34)") (class "Default")
      (node (ref "U2") (pin "34") (pinfunction "P109_34") (pintype "passive+no_connect"))
    )
    (net (code "197") (name "unconnected-(U2-P111-Pad36)") (class "Default")
      (node (ref "U2") (pin "36") (pinfunction "P111_36") (pintype "passive+no_connect"))
    )
    (net (code "198") (name "unconnected-(U2-P112-Pad37)") (class "Default")
      (node (ref "U2") (pin "37") (pinfunction "P112_37") (pintype "passive+no_connect"))
    )
    (net (code "199") (name "unconnected-(U2-P113-Pad38)") (class "Default")
      (node (ref "U2") (pin "38") (pinfunction "P113_38") (pintype "passive+no_connect"))
    )
    (net (code "200") (name "unconnected-(U2-P200-Pad27)") (class "Default")
      (node (ref "U2") (pin "27") (pinfunction "P200_27") (pintype "passive+no_connect"))
    )
    (net (code "201") (name "unconnected-(U2-P201{slash}MD-Pad26)") (class "Default")
      (node (ref "U2") (pin "26") (pinfunction "P201/MD_26") (pintype "passive+no_connect"))
    )
    (net (code "202") (name "unconnected-(U2-P204-Pad24)") (class "Default")
      (node (ref "U2") (pin "24") (pinfunction "P204_24") (pintype "passive+no_connect"))
    )
    (net (code "203") (name "unconnected-(U2-P205-Pad23)") (class "Default")
      (node (ref "U2") (pin "23") (pinfunction "P205_23") (pintype "passive+no_connect"))
    )
    (net (code "204") (name "unconnected-(U2-P206-Pad22)") (class "Default")
      (node (ref "U2") (pin "22") (pinfunction "P206_22") (pintype "passive+no_connect"))
    )
    (net (code "205") (name "unconnected-(U2-P212{slash}EXTAL-Pad10)") (class "Default")
      (node (ref "U2") (pin "10") (pinfunction "P212/EXTAL_10") (pintype "passive+no_connect"))
    )
    (net (code "206") (name "unconnected-(U2-P213{slash}XTAL-Pad9)") (class "Default")
      (node (ref "U2") (pin "9") (pinfunction "P213/XTAL_9") (pintype "passive+no_connect"))
    )
    (net (code "207") (name "unconnected-(U2-P214{slash}XCOUT-Pad7)") (class "Default")
      (node (ref "U2") (pin "7") (pinfunction "P214/XCOUT_7") (pintype "passive+no_connect"))
    )
    (net (code "208") (name "unconnected-(U2-P215{slash}XCIN-Pad6)") (class "Default")
      (node (ref "U2") (pin "6") (pinfunction "P215/XCIN_6") (pintype "passive+no_connect"))
    )
    (net (code "209") (name "unconnected-(U2-P301-Pad31)") (class "Default")
      (node (ref "U2") (pin "31") (pinfunction "P301_31") (pintype "passive+no_connect"))
    )
    (net (code "210") (name "unconnected-(U2-P302-Pad30)") (class "Default")
      (node (ref "U2") (pin "30") (pinfunction "P302_30") (pintype "passive+no_connect"))
    )
    (net (code "211") (name "unconnected-(U2-P303-Pad29)") (class "Default")
      (node (ref "U2") (pin "29") (pinfunction "P303_29") (pintype "passive+no_connect"))
    )
    (net (code "212") (name "unconnected-(U2-P304-Pad28)") (class "Default")
      (node (ref "U2") (pin "28") (pinfunction "P304_28") (pintype "passive+no_connect"))
    )
    (net (code "213") (name "unconnected-(U2-P400-Pad1)") (class "Default")
      (node (ref "U2") (pin "1") (pinfunction "P400_1") (pintype "passive+no_connect"))
    )
    (net (code "214") (name "unconnected-(U2-P401-Pad2)") (class "Default")
      (node (ref "U2") (pin "2") (pinfunction "P401_2") (pintype "passive+no_connect"))
    )
    (net (code "215") (name "unconnected-(U2-P402-Pad3)") (class "Default")
      (node (ref "U2") (pin "3") (pinfunction "P402_3") (pintype "passive+no_connect"))
    )
    (net (code "216") (name "unconnected-(U2-P403-Pad4)") (class "Default")
      (node (ref "U2") (pin "4") (pinfunction "P403_4") (pintype "passive+no_connect"))
    )
    (net (code "217") (name "unconnected-(U2-P408-Pad15)") (class "Default")
      (node (ref "U2") (pin "15") (pinfunction "P408_15") (pintype "passive+no_connect"))
    )
    (net (code "218") (name "unconnected-(U2-P409-Pad14)") (class "Default")
      (node (ref "U2") (pin "14") (pinfunction "P409_14") (pintype "passive+no_connect"))
    )
    (net (code "219") (name "unconnected-(U2-P410-Pad13)") (class "Default")
      (node (ref "U2") (pin "13") (pinfunction "P410_13") (pintype "passive+no_connect"))
    )
    (net (code "220") (name "unconnected-(U2-P411-Pad12)") (class "Default")
      (node (ref "U2") (pin "12") (pinfunction "P411_12") (pintype "passive+no_connect"))
    )
    (net (code "221") (name "unconnected-(U2-P500-Pad49)") (class "Default")
      (node (ref "U2") (pin "49") (pinfunction "P500_49") (pintype "passive+no_connect"))
    )
    (net (code "222") (name "unconnected-(U2-P501-Pad50)") (class "Default")
      (node (ref "U2") (pin "50") (pinfunction "P501_50") (pintype "passive+no_connect"))
    )
    (net (code "223") (name "unconnected-(U2-P502-Pad51)") (class "Default")
      (node (ref "U2") (pin "51") (pinfunction "P502_51") (pintype "passive+no_connect"))
    )
  )
)
